# EEZ_PSU_power_board_r5B6b.net
KiCad netlist of a schematic drawn in EAGLE
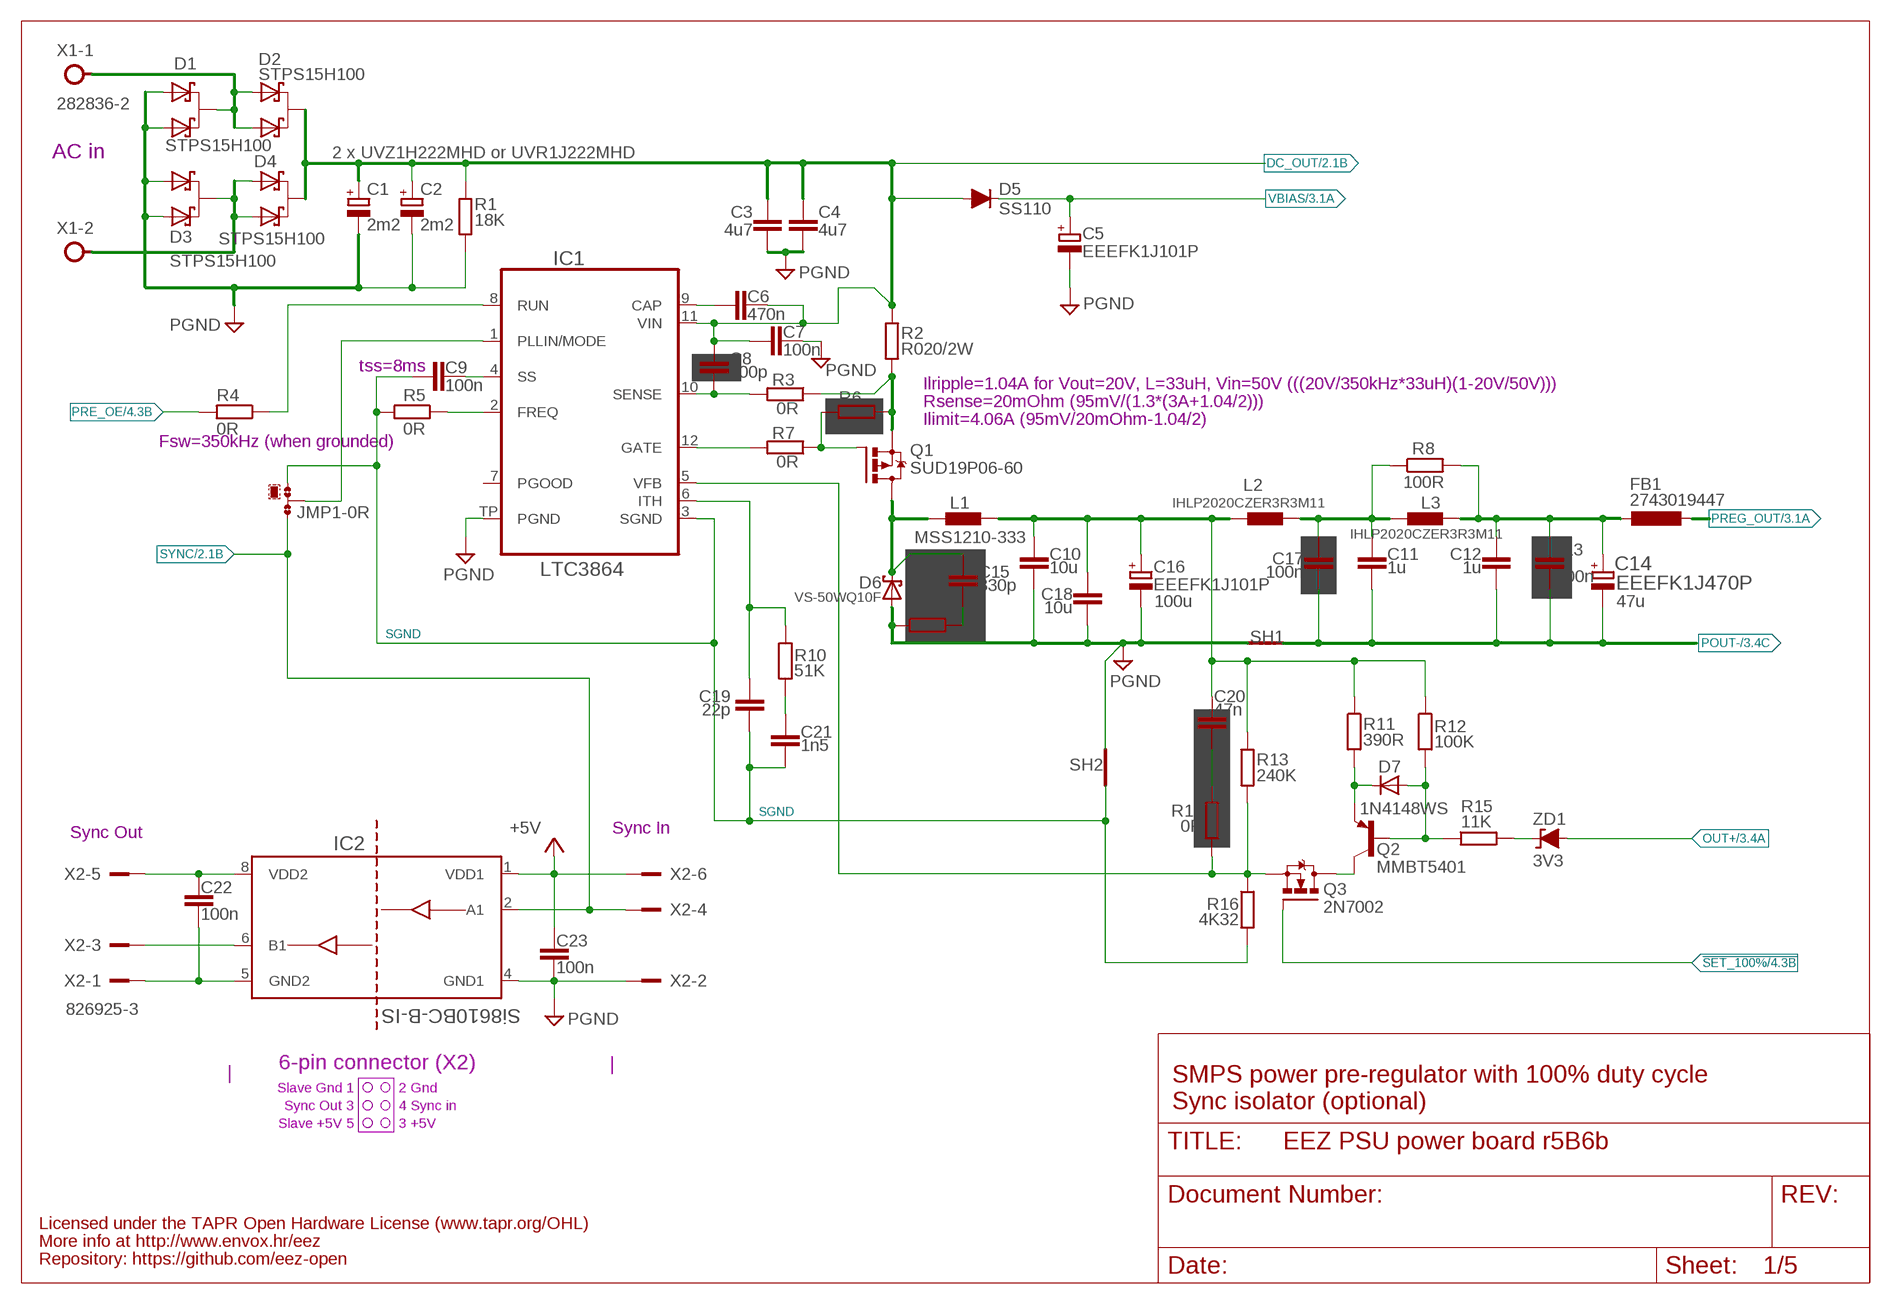
[diagram p0: schematic, sheet 1]
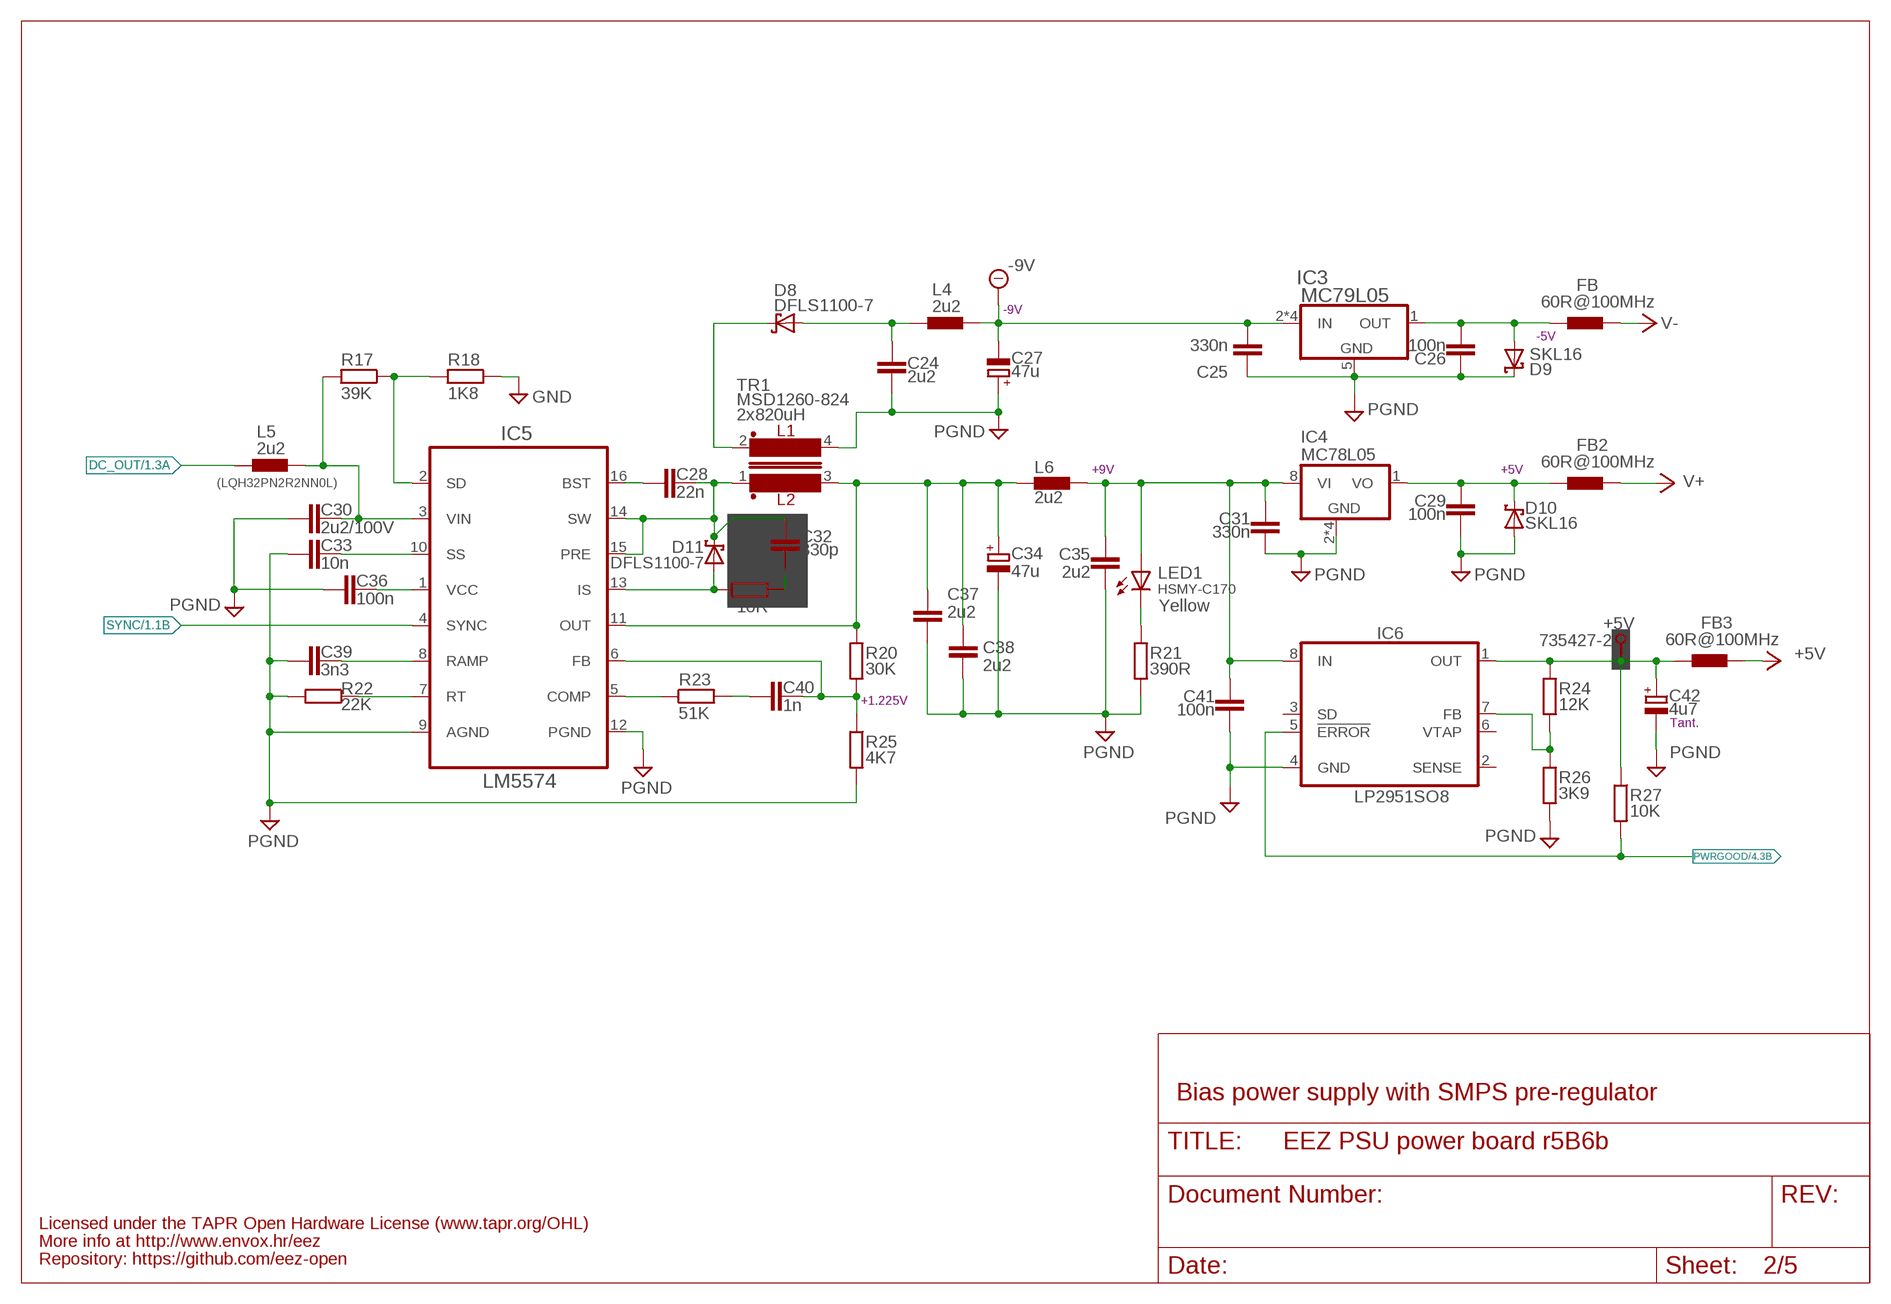
[diagram p1: schematic, sheet 2]
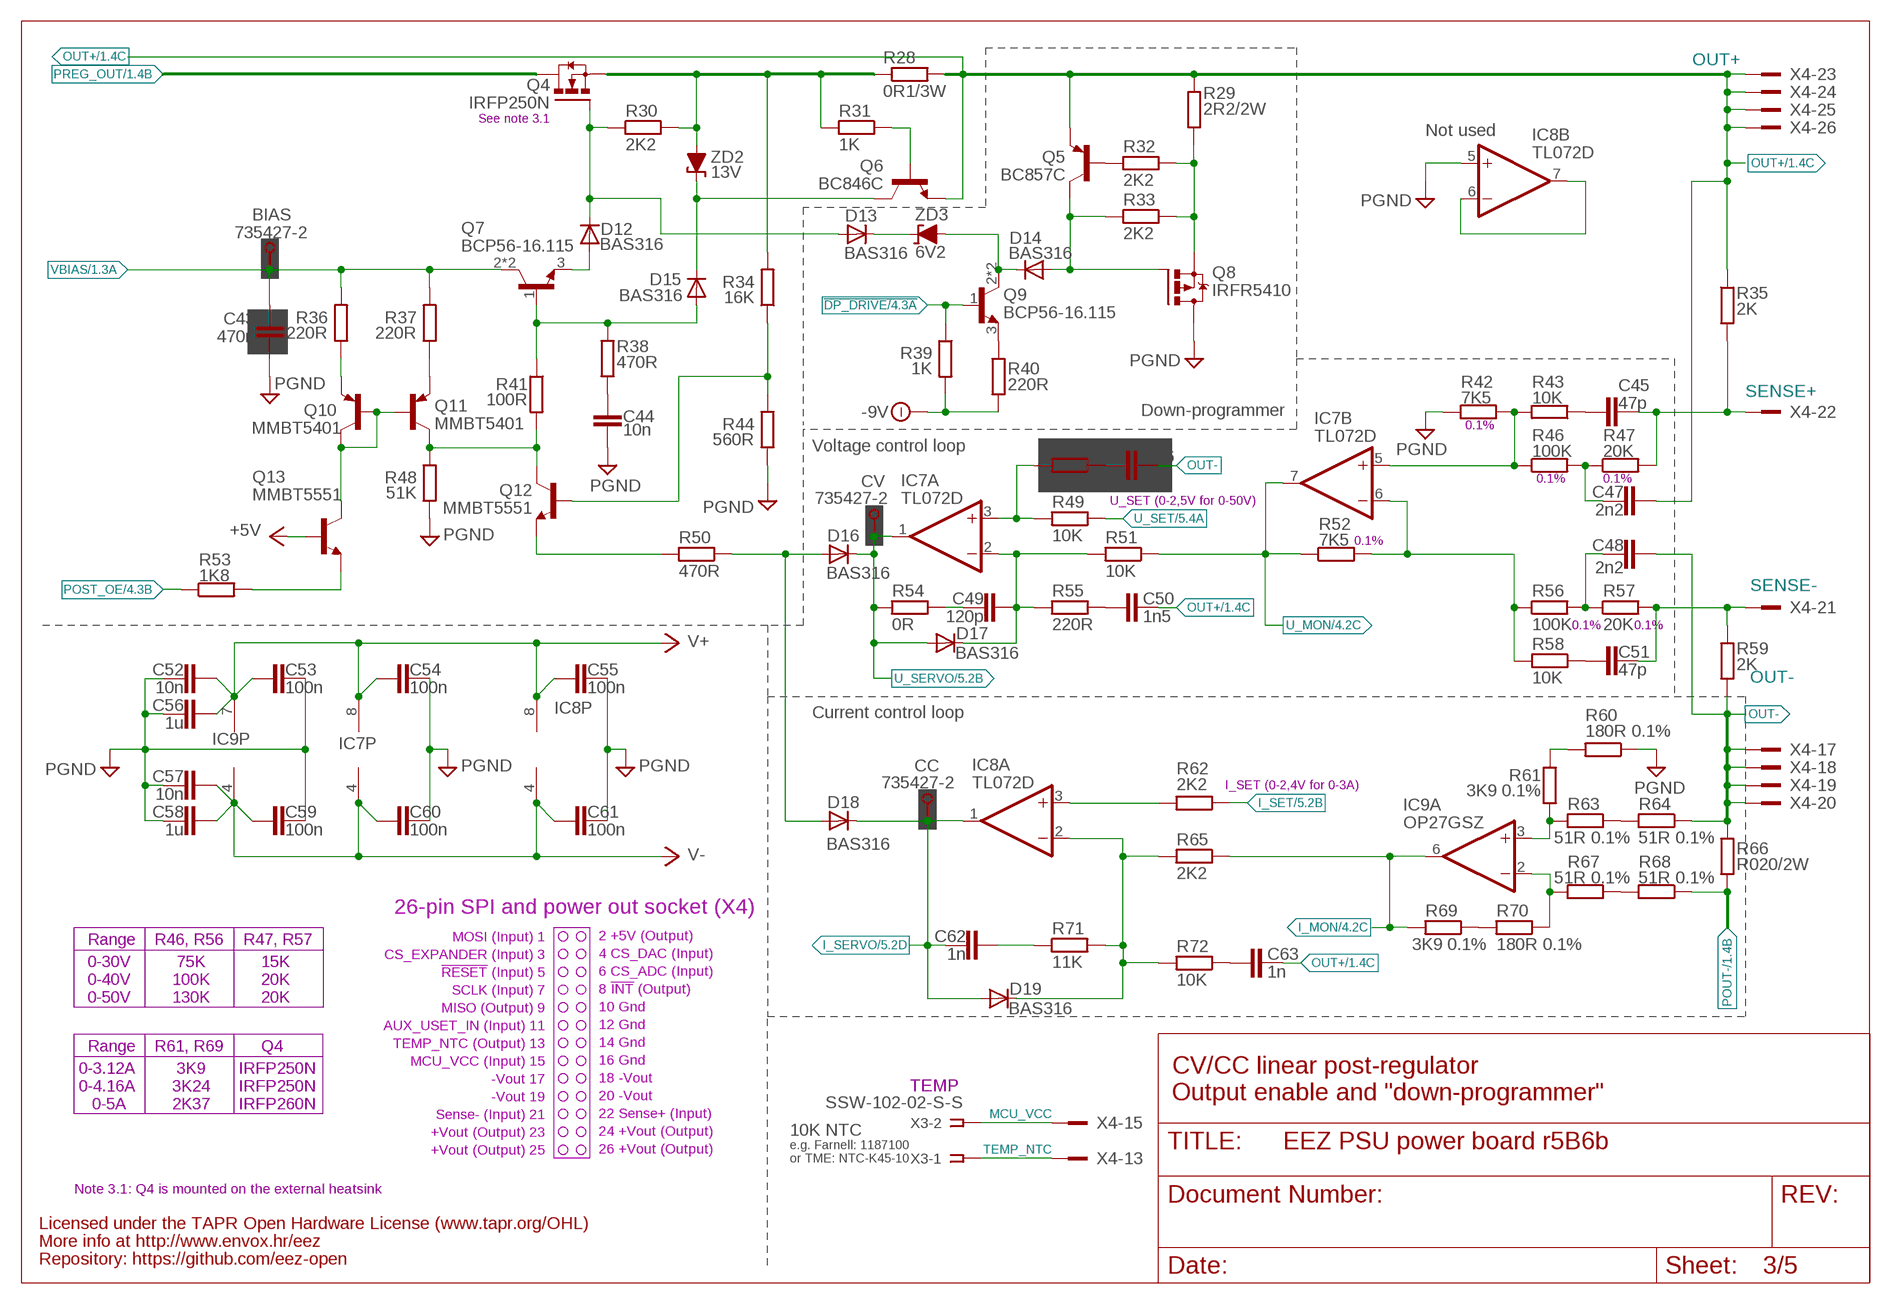
[diagram p2: schematic, sheet 3]
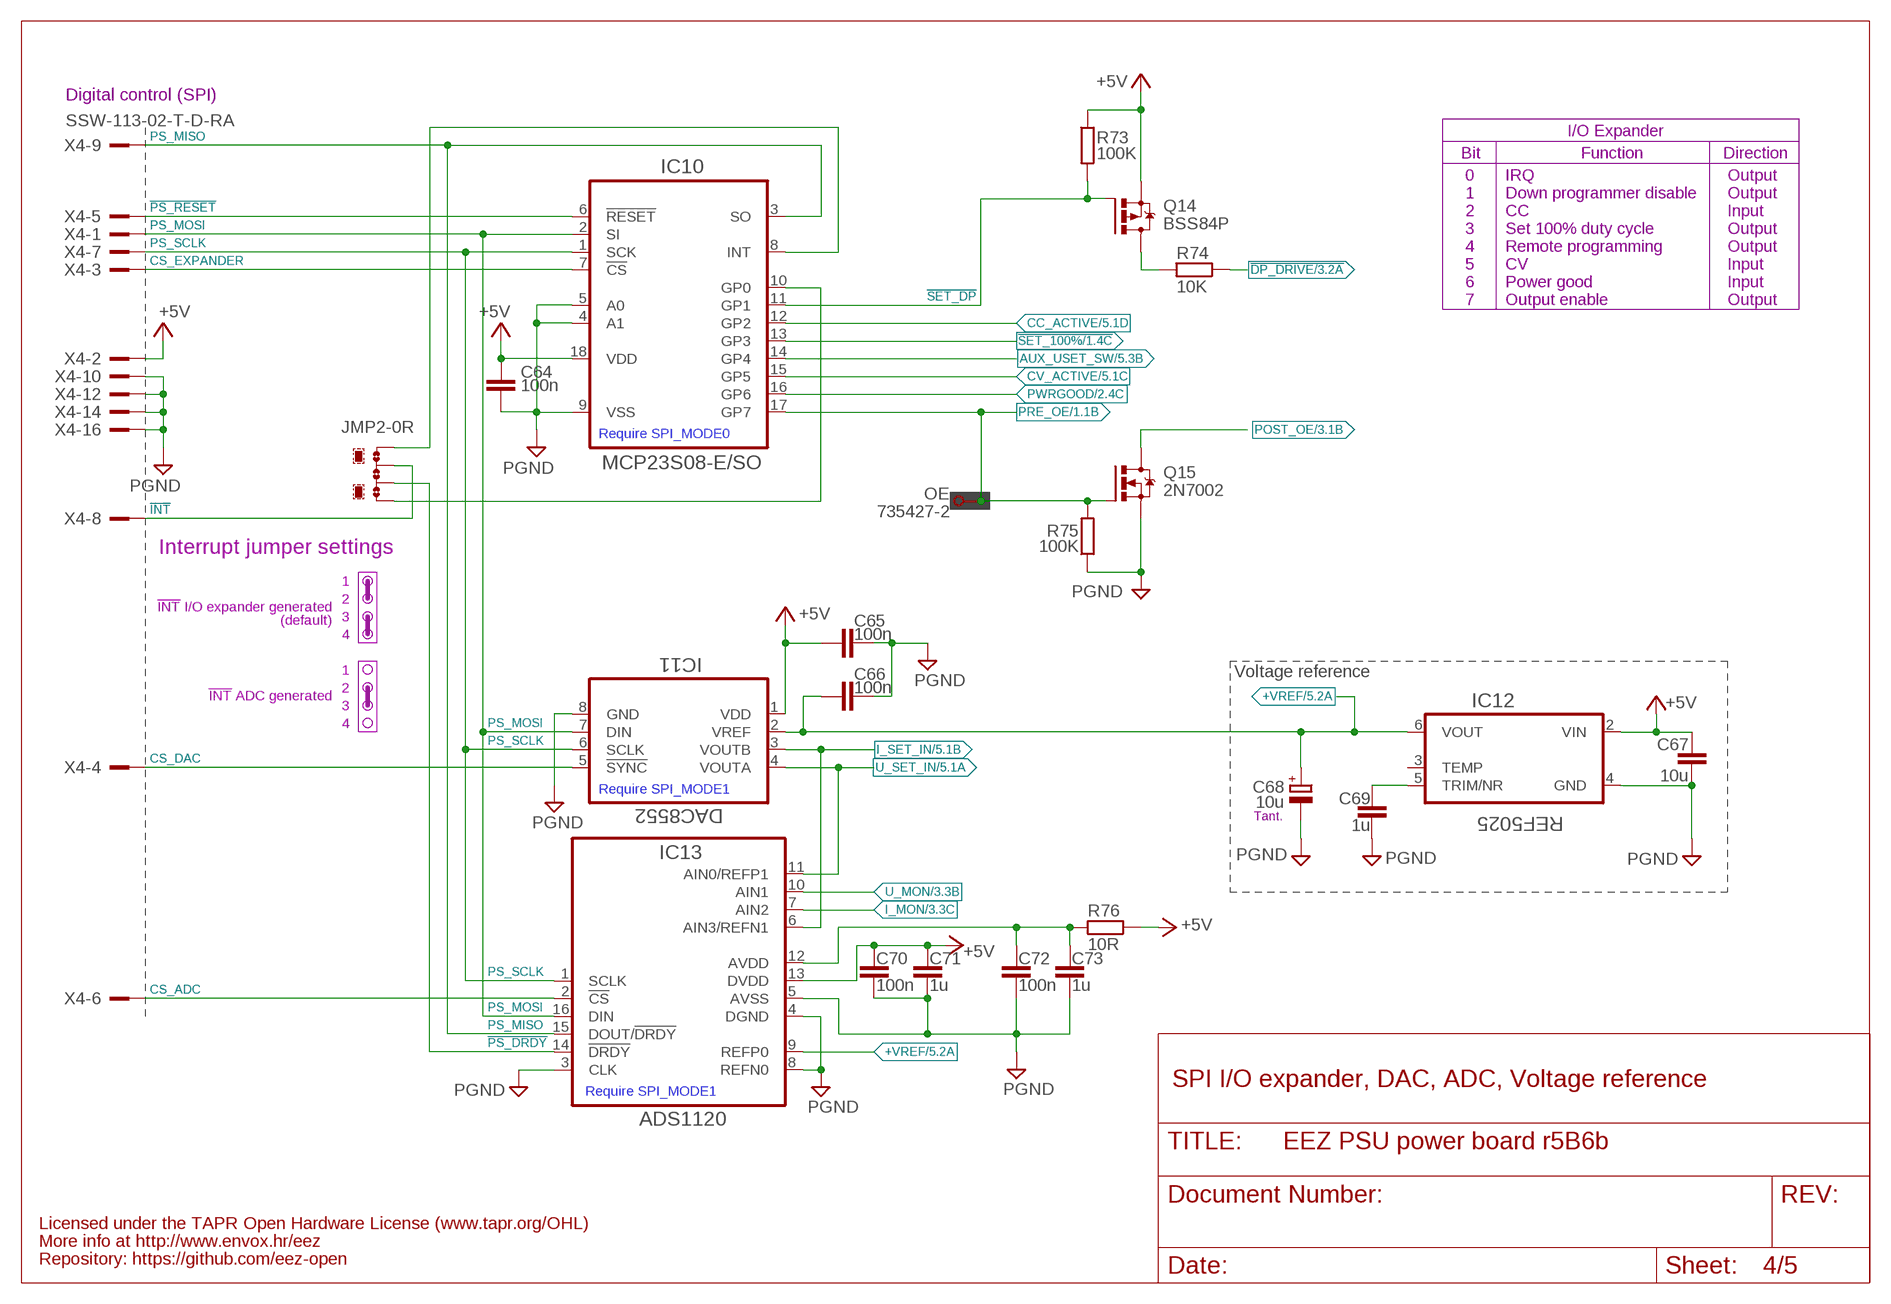
[diagram p3: schematic, sheet 4]
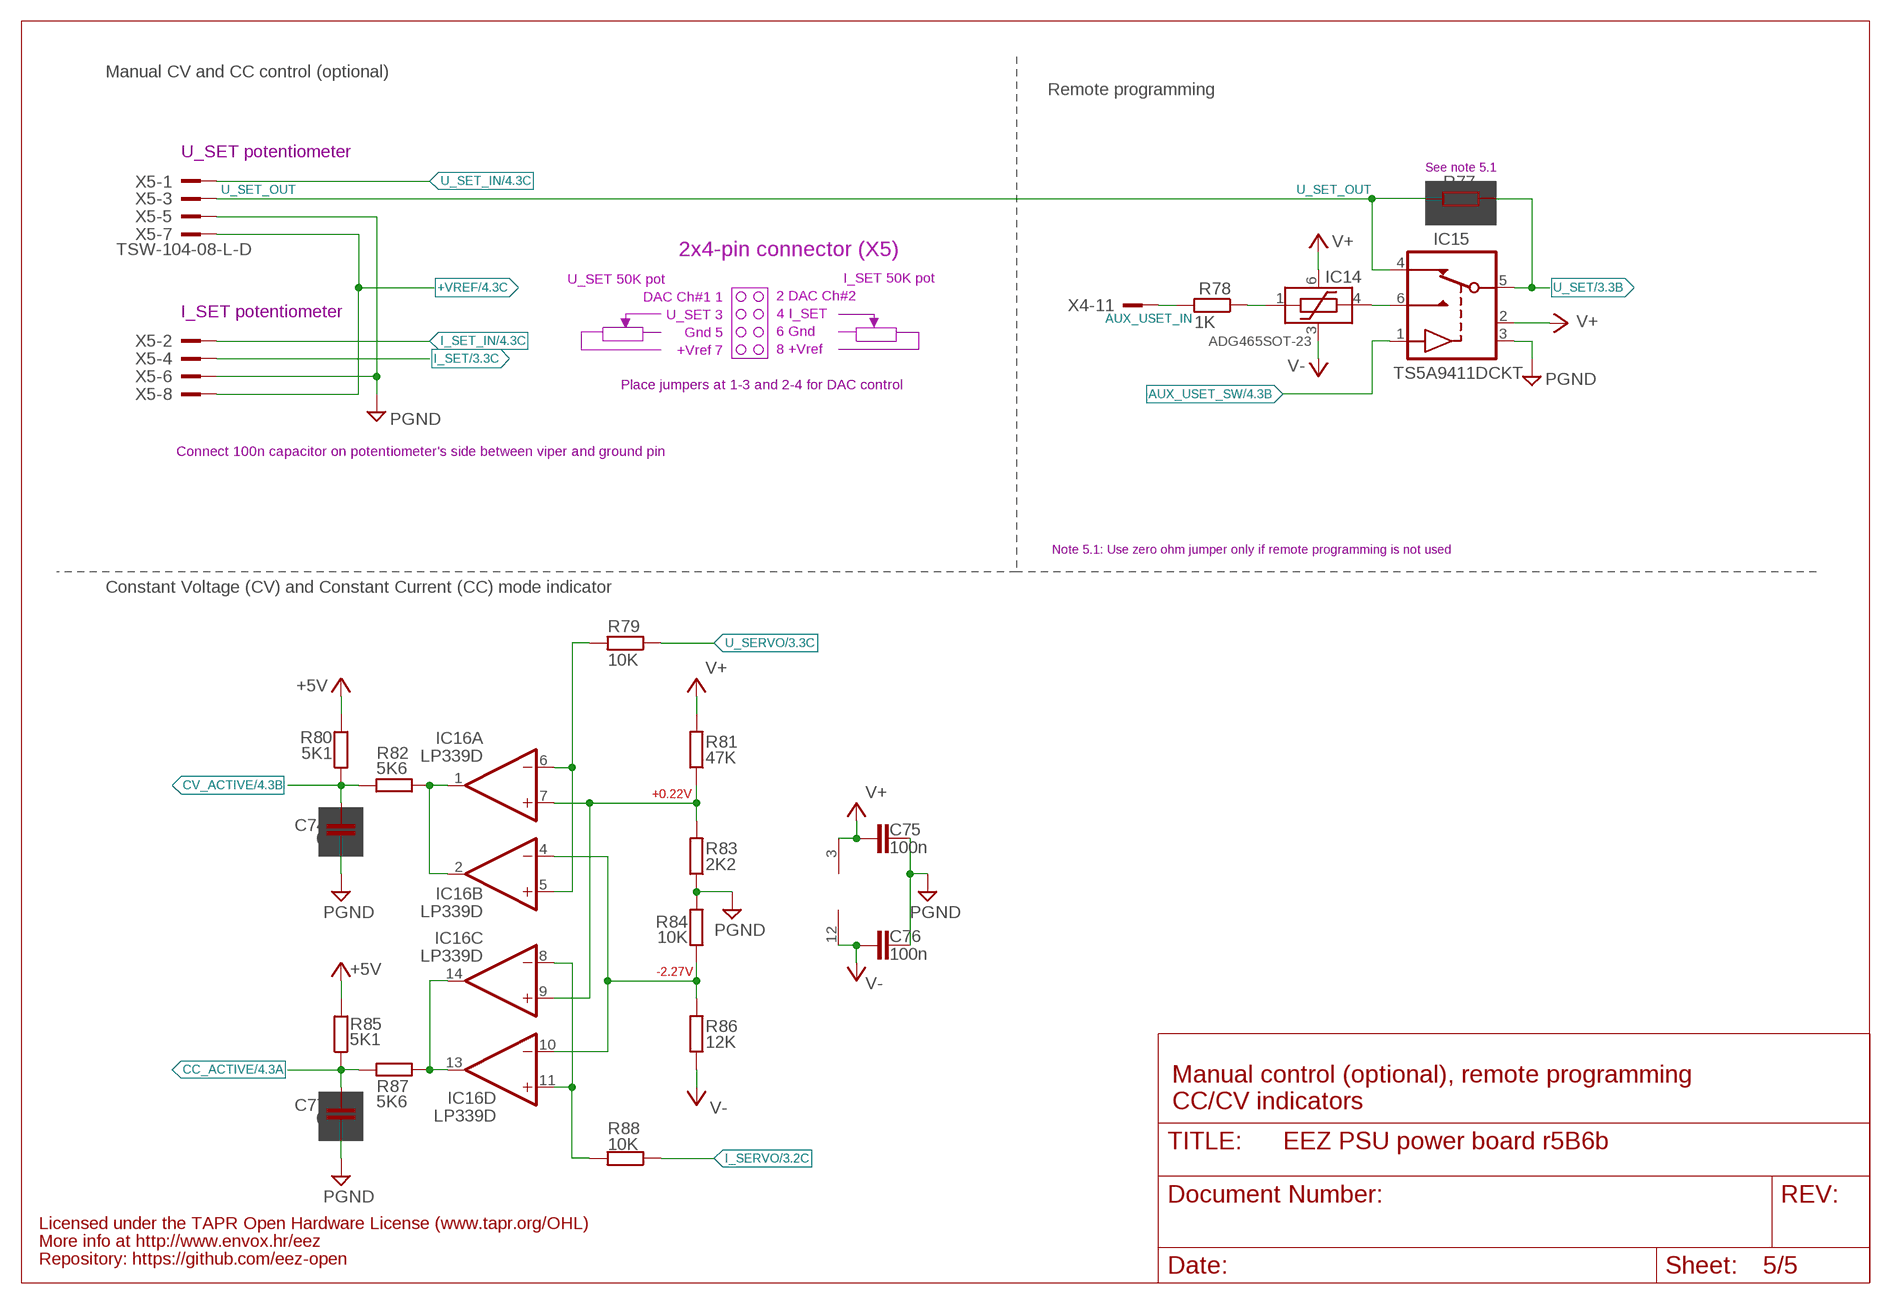
[diagram p4: schematic, sheet 5]

(export (version "E")
  (design (tool "Eeschema 10.0.6"))
  (components
    (comp (ref "C74")
      (value "0")
      (footprint "eagle-import:C0603")
      (libsource (lib "eagle-import") (part "C-EUC0603"))
    )
    (comp (ref "C75")
      (value "100n")
      (footprint "eagle-import:C0603")
      (libsource (lib "eagle-import") (part "C-EUC0603"))
    )
    (comp (ref "C76")
      (value "100n")
      (footprint "eagle-import:C0603")
      (libsource (lib "eagle-import") (part "C-EUC0603"))
    )
    (comp (ref "C77")
      (value "0")
      (footprint "eagle-import:C0603")
      (libsource (lib "eagle-import") (part "C-EUC0603"))
    )
    (comp (ref "IC14")
      (value "ADG465SOT-23")
      (footprint "eagle-import:SOT95P280X145-6N")
      (libsource (lib "eagle-import") (part "ADG465SOT-23"))
    )
    (comp (ref "IC15")
      (value "TS5A9411DCKT")
      (footprint "eagle-import:SOT65P210X110-6N")
      (libsource (lib "eagle-import") (part "TS5A9411DCKT"))
    )
    (comp (ref "IC16")
      (value "LP339D")
      (footprint "eagle-import:SOIC127P600X175-14N")
      (libsource (lib "eagle-import") (part "LM339SO14"))
    )
    (comp (ref "R77")
      (value "0R")
      (footprint "eagle-import:R0805")
      (libsource (lib "eagle-import") (part "R-EU_R0805"))
    )
    (comp (ref "R78")
      (value "1K")
      (footprint "eagle-import:R0805")
      (libsource (lib "eagle-import") (part "R-EU_R0805"))
    )
    (comp (ref "R79")
      (value "10K")
      (footprint "eagle-import:R0805")
      (libsource (lib "eagle-import") (part "R-EU_R0805"))
    )
    (comp (ref "R80")
      (value "5K1")
      (footprint "eagle-import:R0805")
      (libsource (lib "eagle-import") (part "R-EU_R0805"))
    )
    (comp (ref "R81")
      (value "47K")
      (footprint "eagle-import:R0805")
      (libsource (lib "eagle-import") (part "R-EU_R0805"))
    )
    (comp (ref "R82")
      (value "5K6")
      (footprint "eagle-import:R0805")
      (libsource (lib "eagle-import") (part "R-EU_R0805"))
    )
    (comp (ref "R83")
      (value "2K2")
      (footprint "eagle-import:R0805")
      (libsource (lib "eagle-import") (part "R-EU_R0805"))
    )
    (comp (ref "R84")
      (value "10K")
      (footprint "eagle-import:R0805")
      (libsource (lib "eagle-import") (part "R-EU_R0805"))
    )
    (comp (ref "R85")
      (value "5K1")
      (footprint "eagle-import:R0805")
      (libsource (lib "eagle-import") (part "R-EU_R0805"))
    )
    (comp (ref "R86")
      (value "12K")
      (footprint "eagle-import:R0805")
      (libsource (lib "eagle-import") (part "R-EU_R0805"))
    )
    (comp (ref "R87")
      (value "5K6")
      (footprint "eagle-import:R0805")
      (libsource (lib "eagle-import") (part "R-EU_R0805"))
    )
    (comp (ref "R88")
      (value "10K")
      (footprint "eagle-import:R0805")
      (libsource (lib "eagle-import") (part "R-EU_R0805"))
    )
    (comp (ref "X4")
      (value "SSW-113-02-T-D-RA")
      (footprint "eagle-import:SSW-113-02-T-D-RA")
      (fields (field (name "FARNELL") "1805583"))
      (libsource (lib "eagle-import") (part "SSW-113-02-T-D-RA"))
    )
    (comp (ref "X5")
      (value "TSW-104-08-L-D")
      (footprint "eagle-import:TSW-104-02-S-D")
      (libsource (lib "eagle-import") (part "TSW-104-02-S-D"))
    )
    (comp (ref "C1")
      (value "2m2")
      (footprint "eagle-import:ECAP7.5_18")
      (libsource (lib "eagle-import") (part "ECAP7.5G_18MM"))
    )
    (comp (ref "C2")
      (value "2m2")
      (footprint "eagle-import:ECAP7.5_18")
      (libsource (lib "eagle-import") (part "ECAP7.5G_18MM"))
    )
    (comp (ref "C3")
      (value "4u7")
      (footprint "eagle-import:C1210")
      (libsource (lib "eagle-import") (part "C-EUC1210"))
    )
    (comp (ref "C4")
      (value "4u7")
      (footprint "eagle-import:C1210")
      (libsource (lib "eagle-import") (part "C-EUC1210"))
    )
    (comp (ref "C5")
      (value "EEEFK1J101P")
      (footprint "eagle-import:ECAP5_10.5+PANASONIC_F")
      (libsource (lib "eagle-import") (part "ECAP5G_10.5MM_F"))
    )
    (comp (ref "C6")
      (value "470n")
      (footprint "eagle-import:C0805")
      (libsource (lib "eagle-import") (part "C-EUC0805"))
    )
    (comp (ref "C7")
      (value "100n")
      (footprint "eagle-import:C0805")
      (libsource (lib "eagle-import") (part "C-EUC0805"))
    )
    (comp (ref "C8")
      (value "100p")
      (footprint "eagle-import:C0805")
      (libsource (lib "eagle-import") (part "C-EUC0805"))
    )
    (comp (ref "C9")
      (value "100n")
      (footprint "eagle-import:C0805")
      (libsource (lib "eagle-import") (part "C-EUC0805"))
    )
    (comp (ref "C10")
      (value "10u")
      (footprint "eagle-import:C1210")
      (libsource (lib "eagle-import") (part "C-EUC1210"))
    )
    (comp (ref "C11")
      (value "1u")
      (footprint "eagle-import:C1206")
      (libsource (lib "eagle-import") (part "resistor_C-EUC1206"))
    )
    (comp (ref "C12")
      (value "1u")
      (footprint "eagle-import:C1206")
      (libsource (lib "eagle-import") (part "resistor_C-EUC1206"))
    )
    (comp (ref "C13")
      (value "100n")
      (footprint "eagle-import:C0805")
      (libsource (lib "eagle-import") (part "C-EUC0805"))
    )
    (comp (ref "C14")
      (value "EEEFK1J470P")
      (footprint "eagle-import:CAPAE830X1050N")
      (fields (field (name "MPN") "EEE-FK1J470P") (field (name "TOLERANCE") "±20 %"))
      (libsource (lib "eagle-import") (part "EEE--CASE-FFK1J470P"))
    )
    (comp (ref "C15")
      (value "330p")
      (footprint "eagle-import:C0805")
      (libsource (lib "eagle-import") (part "C-EUC0805"))
    )
    (comp (ref "C16")
      (value "EEEFK1J101P")
      (footprint "eagle-import:ECAP5_10.5+PANASONIC_F")
      (libsource (lib "eagle-import") (part "ECAP5G_10.5MM_F"))
    )
    (comp (ref "C17")
      (value "100n")
      (footprint "eagle-import:C0805")
      (libsource (lib "eagle-import") (part "C-EUC0805"))
    )
    (comp (ref "C18")
      (value "10u")
      (footprint "eagle-import:C1210")
      (libsource (lib "eagle-import") (part "C-EUC1210"))
    )
    (comp (ref "C19")
      (value "22p")
      (footprint "eagle-import:C0805")
      (libsource (lib "eagle-import") (part "C-EUC0805"))
    )
    (comp (ref "C20")
      (value "47n")
      (footprint "eagle-import:C0805")
      (libsource (lib "eagle-import") (part "C-EUC0805"))
    )
    (comp (ref "C21")
      (value "1n5")
      (footprint "eagle-import:C0805")
      (libsource (lib "eagle-import") (part "C-EUC0805"))
    )
    (comp (ref "C22")
      (value "100n")
      (footprint "eagle-import:C0603")
      (libsource (lib "eagle-import") (part "C-EUC0603"))
    )
    (comp (ref "C23")
      (value "100n")
      (footprint "eagle-import:C0603")
      (libsource (lib "eagle-import") (part "C-EUC0603"))
    )
    (comp (ref "D1")
      (value "STPS15H100")
      (footprint "eagle-import:TO252@1")
      (libsource (lib "eagle-import") (part "VS-6CWQ06FNPBF"))
    )
    (comp (ref "D2")
      (value "STPS15H100")
      (footprint "eagle-import:TO252@1")
      (libsource (lib "eagle-import") (part "VS-6CWQ06FNPBF"))
    )
    (comp (ref "D3")
      (value "STPS15H100")
      (footprint "eagle-import:TO252@1")
      (libsource (lib "eagle-import") (part "VS-6CWQ06FNPBF"))
    )
    (comp (ref "D4")
      (value "STPS15H100")
      (footprint "eagle-import:TO252@1")
      (libsource (lib "eagle-import") (part "VS-6CWQ06FNPBF"))
    )
    (comp (ref "D5")
      (value "SS110")
      (footprint "eagle-import:DO214AA")
      (libsource (lib "eagle-import") (part "DIODEDO214AA"))
    )
    (comp (ref "D6")
      (value "VS-50WQ10F")
      (footprint "eagle-import:TO252@1")
      (libsource (lib "eagle-import") (part "SCHOTTKYTO252"))
    )
    (comp (ref "D7")
      (value "1N4148WS")
      (footprint "eagle-import:SOD323-W")
      (libsource (lib "eagle-import") (part "DIODE-SOD323-W"))
    )
    (comp (ref "FB1")
      (value "2743019447")
      (footprint "eagle-import:L1812")
      (libsource (lib "eagle-import") (part "L-EUL1812"))
    )
    (comp (ref "IC1")
      (value "LTC3864")
      (footprint "eagle-import:LTC_05-08-1666")
      (libsource (lib "eagle-import") (part "LTC3864"))
    )
    (comp (ref "IC2")
      (value "Si8610BC-B-IS")
      (footprint "eagle-import:SOIC127P600X173-8N")
      (libsource (lib "eagle-import") (part "SI8610"))
    )
    (comp (ref "JMP1")
      (value "0R-JUMPA")
      (footprint "eagle-import:A0R-JMP")
      (libsource (lib "eagle-import") (part "0R-JUMPA"))
    )
    (comp (ref "L1")
      (value "MSS1210-333")
      (footprint "eagle-import:MSS1210")
      (libsource (lib "eagle-import") (part "COILCRAFT_MSS1210"))
    )
    (comp (ref "L2")
      (value "IHLP2020CZER3R3M11")
      (footprint "eagle-import:IHLP-2020BZ-11")
      (libsource (lib "eagle-import") (part "IHLP-2020BZ-11"))
    )
    (comp (ref "L3")
      (value "IHLP2020CZER3R3M11")
      (footprint "eagle-import:IHLP-2020BZ-11")
      (libsource (lib "eagle-import") (part "IHLP-2020BZ-11"))
    )
    (comp (ref "Q1")
      (value "SUD19P06-60")
      (footprint "eagle-import:TO229P990X239-3N")
      (libsource (lib "eagle-import") (part "P-MOSFETDPAK"))
    )
    (comp (ref "Q2")
      (value "MMBT5401")
      (footprint "eagle-import:SOT23-BEC")
      (libsource (lib "eagle-import") (part "-PNP-SOT23-BECBC857B"))
    )
    (comp (ref "Q3")
      (value "2N7002")
      (footprint "eagle-import:SOT103P240X110-3N")
      (fields (field (name "MPN") "2N7002-7-F"))
      (libsource (lib "eagle-import") (part "2N7002"))
    )
    (comp (ref "R1")
      (value "18K")
      (footprint "eagle-import:R1206")
      (libsource (lib "eagle-import") (part "R-EU_R1206"))
    )
    (comp (ref "R2")
      (value "R020/2W")
      (footprint "eagle-import:R2512")
      (libsource (lib "eagle-import") (part "R-EU_R2512"))
    )
    (comp (ref "R3")
      (value "0R")
      (footprint "eagle-import:R0805")
      (libsource (lib "eagle-import") (part "R-EU_R0805"))
    )
    (comp (ref "R4")
      (value "0R")
      (footprint "eagle-import:R0805")
      (libsource (lib "eagle-import") (part "R-EU_R0805"))
    )
    (comp (ref "R5")
      (value "0R")
      (footprint "eagle-import:R0805")
      (libsource (lib "eagle-import") (part "R-EU_R0805"))
    )
    (comp (ref "R6")
      (value "100K")
      (footprint "eagle-import:R0805")
      (libsource (lib "eagle-import") (part "R-EU_R0805"))
    )
    (comp (ref "R7")
      (value "0R")
      (footprint "eagle-import:R0805")
      (libsource (lib "eagle-import") (part "R-EU_R0805"))
    )
    (comp (ref "R8")
      (value "100R")
      (footprint "eagle-import:R0805")
      (libsource (lib "eagle-import") (part "R-EU_R0805"))
    )
    (comp (ref "R9")
      (value "10R")
      (footprint "eagle-import:R1206")
      (libsource (lib "eagle-import") (part "R-EU_R1206"))
    )
    (comp (ref "R10")
      (value "51K")
      (footprint "eagle-import:R0805")
      (libsource (lib "eagle-import") (part "R-EU_R0805"))
    )
    (comp (ref "R11")
      (value "390R")
      (footprint "eagle-import:R0805")
      (libsource (lib "eagle-import") (part "R-EU_R0805"))
    )
    (comp (ref "R12")
      (value "100K")
      (footprint "eagle-import:R0805")
      (libsource (lib "eagle-import") (part "R-EU_R0805"))
    )
    (comp (ref "R13")
      (value "240K")
      (footprint "eagle-import:R0805")
      (libsource (lib "eagle-import") (part "R-EU_R0805"))
    )
    (comp (ref "R14")
      (value "0R")
      (footprint "eagle-import:R0805")
      (libsource (lib "eagle-import") (part "R-EU_R0805"))
    )
    (comp (ref "R15")
      (value "11K")
      (footprint "eagle-import:R0805")
      (libsource (lib "eagle-import") (part "R-EU_R0805"))
    )
    (comp (ref "R16")
      (value "4K32")
      (footprint "eagle-import:R0805")
      (libsource (lib "eagle-import") (part "R-EU_R0805"))
    )
    (comp (ref "SH1")
      (value "Pgnd to Pout- short")
      (footprint "eagle-import:SHORT")
      (libsource (lib "eagle-import") (part "SHORT"))
    )
    (comp (ref "SH2")
      (value "Sgnd to Pgnd short")
      (footprint "eagle-import:SHORT")
      (libsource (lib "eagle-import") (part "SHORT"))
    )
    (comp (ref "X1")
      (value "282836-2")
      (footprint "eagle-import:TBLOCK5.0_2")
      (libsource (lib "eagle-import") (part "TBLOCK5.0_2A"))
    )
    (comp (ref "X2")
      (value "826925-3")
      (footprint "eagle-import:TSW-103-07-F-D")
      (libsource (lib "eagle-import") (part "TSW-103-07-F-D"))
    )
    (comp (ref "ZD1")
      (value "3V3")
      (footprint "eagle-import:MINIMELF")
      (libsource (lib "eagle-import") (part "ZENER-DIODEMINIMELF"))
    )
    (comp (ref "BIAS")
      (value "735427-2")
      (footprint "eagle-import:PCB_SHIELD_TAB")
      (libsource (lib "eagle-import") (part "PCB_TEST_TABSHIELD"))
    )
    (comp (ref "C43")
      (value "470n")
      (footprint "eagle-import:C1812")
      (libsource (lib "eagle-import") (part "C-EUC1812"))
    )
    (comp (ref "C44")
      (value "10n")
      (footprint "eagle-import:C0805")
      (libsource (lib "eagle-import") (part "C-EUC0805"))
    )
    (comp (ref "C45")
      (value "47p")
      (footprint "eagle-import:C0805")
      (libsource (lib "eagle-import") (part "C-EUC0805"))
    )
    (comp (ref "C46")
      (value "1n5")
      (footprint "eagle-import:C0805")
      (libsource (lib "eagle-import") (part "C-EUC0805"))
    )
    (comp (ref "C47")
      (value "2n2")
      (footprint "eagle-import:C0805")
      (libsource (lib "eagle-import") (part "C-EUC0805"))
    )
    (comp (ref "C48")
      (value "2n2")
      (footprint "eagle-import:C0805")
      (libsource (lib "eagle-import") (part "C-EUC0805"))
    )
    (comp (ref "C49")
      (value "120p")
      (footprint "eagle-import:C0805")
      (libsource (lib "eagle-import") (part "C-EUC0805"))
    )
    (comp (ref "C50")
      (value "1n5")
      (footprint "eagle-import:C0805")
      (libsource (lib "eagle-import") (part "C-EUC0805"))
    )
    (comp (ref "C51")
      (value "47p")
      (footprint "eagle-import:C0805")
      (libsource (lib "eagle-import") (part "C-EUC0805"))
    )
    (comp (ref "C52")
      (value "10n")
      (footprint "eagle-import:C0805")
      (libsource (lib "eagle-import") (part "C-EUC0805"))
    )
    (comp (ref "C53")
      (value "100n")
      (footprint "eagle-import:C0603")
      (libsource (lib "eagle-import") (part "C-EUC0603"))
    )
    (comp (ref "C54")
      (value "100n")
      (footprint "eagle-import:C0603")
      (libsource (lib "eagle-import") (part "C-EUC0603"))
    )
    (comp (ref "C55")
      (value "100n")
      (footprint "eagle-import:C0603")
      (libsource (lib "eagle-import") (part "C-EUC0603"))
    )
    (comp (ref "C56")
      (value "1u")
      (footprint "eagle-import:C0805")
      (libsource (lib "eagle-import") (part "C-EUC0805"))
    )
    (comp (ref "C57")
      (value "10n")
      (footprint "eagle-import:C0805")
      (libsource (lib "eagle-import") (part "C-EUC0805"))
    )
    (comp (ref "C58")
      (value "1u")
      (footprint "eagle-import:C0805")
      (libsource (lib "eagle-import") (part "C-EUC0805"))
    )
    (comp (ref "C59")
      (value "100n")
      (footprint "eagle-import:C0603")
      (libsource (lib "eagle-import") (part "C-EUC0603"))
    )
    (comp (ref "C60")
      (value "100n")
      (footprint "eagle-import:C0603")
      (libsource (lib "eagle-import") (part "C-EUC0603"))
    )
    (comp (ref "C61")
      (value "100n")
      (footprint "eagle-import:C0603")
      (libsource (lib "eagle-import") (part "C-EUC0603"))
    )
    (comp (ref "C62")
      (value "1n")
      (footprint "eagle-import:C0805")
      (libsource (lib "eagle-import") (part "C-EUC0805"))
    )
    (comp (ref "C63")
      (value "1n")
      (footprint "eagle-import:C0805")
      (libsource (lib "eagle-import") (part "C-EUC0805"))
    )
    (comp (ref "CC")
      (value "735427-2")
      (footprint "eagle-import:PCB_SHIELD_TAB")
      (libsource (lib "eagle-import") (part "PCB_TEST_TABSHIELD"))
    )
    (comp (ref "CV")
      (value "735427-2")
      (footprint "eagle-import:PCB_SHIELD_TAB")
      (libsource (lib "eagle-import") (part "PCB_TEST_TABSHIELD"))
    )
    (comp (ref "D12")
      (value "BAS316")
      (footprint "eagle-import:SOD323-W")
      (libsource (lib "eagle-import") (part "DIODE-SOD323-W"))
    )
    (comp (ref "D13")
      (value "BAS316")
      (footprint "eagle-import:SOD323-W")
      (libsource (lib "eagle-import") (part "DIODE-SOD323-W"))
    )
    (comp (ref "D14")
      (value "BAS316")
      (footprint "eagle-import:SOD323-W")
      (libsource (lib "eagle-import") (part "DIODE-SOD323-W"))
    )
    (comp (ref "D15")
      (value "BAS316")
      (footprint "eagle-import:SOD323-W")
      (libsource (lib "eagle-import") (part "DIODE-SOD323-W"))
    )
    (comp (ref "D16")
      (value "BAS316")
      (footprint "eagle-import:SOD323-W")
      (libsource (lib "eagle-import") (part "DIODE-SOD323-W"))
    )
    (comp (ref "D17")
      (value "BAS316")
      (footprint "eagle-import:SOD323-W")
      (libsource (lib "eagle-import") (part "DIODE-SOD323-W"))
    )
    (comp (ref "D18")
      (value "BAS316")
      (footprint "eagle-import:SOD323-W")
      (libsource (lib "eagle-import") (part "DIODE-SOD323-W"))
    )
    (comp (ref "D19")
      (value "BAS316")
      (footprint "eagle-import:SOD323-W")
      (libsource (lib "eagle-import") (part "DIODE-SOD323-W"))
    )
    (comp (ref "IC7")
      (value "TL072D")
      (footprint "eagle-import:SOIC127P600X173-8N")
      (libsource (lib "eagle-import") (part "TL072SOIC8"))
    )
    (comp (ref "IC8")
      (value "TL072D")
      (footprint "eagle-import:SOIC127P600X173-8N")
      (libsource (lib "eagle-import") (part "TL072SOIC8"))
    )
    (comp (ref "IC9")
      (value "OP27GSZ")
      (footprint "eagle-import:SOIC127P600X173-8N")
      (libsource (lib "eagle-import") (part "OP27GSZSO8"))
    )
    (comp (ref "Q4")
      (value "IRFP250N")
      (footprint "eagle-import:TO247BH-CLR")
      (libsource (lib "eagle-import") (part "IRFP240BOTTOM"))
    )
    (comp (ref "Q5")
      (value "BC857C")
      (footprint "eagle-import:SOT23-BEC")
      (libsource (lib "eagle-import") (part "-PNP-SOT23-BECBC857C"))
    )
    (comp (ref "Q6")
      (value "BC846C")
      (footprint "eagle-import:SOT23-BEC")
      (libsource (lib "eagle-import") (part "-NPN-SOT23-BECBC846B"))
    )
    (comp (ref "Q7")
      (value "BCP56-16.115")
      (footprint "eagle-import:SOT230P700X180-4N")
      (libsource (lib "eagle-import") (part "BCP56"))
    )
    (comp (ref "Q8")
      (value "IRFR5410")
      (footprint "eagle-import:TO229P990X239-3N")
      (libsource (lib "eagle-import") (part "P-MOSFETDPAK"))
    )
    (comp (ref "Q9")
      (value "BCP56-16.115")
      (footprint "eagle-import:SOT230P700X180-4N")
      (libsource (lib "eagle-import") (part "BCP56"))
    )
    (comp (ref "Q10")
      (value "MMBT5401")
      (footprint "eagle-import:SOT23-BEC")
      (libsource (lib "eagle-import") (part "-PNP-SOT23-BECBC857B"))
    )
    (comp (ref "Q11")
      (value "MMBT5401")
      (footprint "eagle-import:SOT23-BEC")
      (libsource (lib "eagle-import") (part "-PNP-SOT23-BECBC857B"))
    )
    (comp (ref "Q12")
      (value "MMBT5551")
      (footprint "eagle-import:SOT23-BEC")
      (libsource (lib "eagle-import") (part "-NPN-SOT23-BECMMBT5551LT1"))
    )
    (comp (ref "Q13")
      (value "MMBT5551")
      (footprint "eagle-import:SOT23-BEC")
      (libsource (lib "eagle-import") (part "-NPN-SOT23-BECMMBT5551LT1"))
    )
    (comp (ref "R28")
      (value "0R1/3W")
      (footprint "eagle-import:R_2512+0411_15")
      (libsource (lib "eagle-import") (part "R_EUCOMBO"))
    )
    (comp (ref "R29")
      (value "2R2/2W")
      (footprint "eagle-import:R_2512+0411_15")
      (libsource (lib "eagle-import") (part "R_EUCOMBO"))
    )
    (comp (ref "R30")
      (value "2K2")
      (footprint "eagle-import:R0805")
      (libsource (lib "eagle-import") (part "R-EU_R0805"))
    )
    (comp (ref "R31")
      (value "1K")
      (footprint "eagle-import:R0805")
      (libsource (lib "eagle-import") (part "R-EU_R0805"))
    )
    (comp (ref "R32")
      (value "2K2")
      (footprint "eagle-import:R0805")
      (libsource (lib "eagle-import") (part "R-EU_R0805"))
    )
    (comp (ref "R33")
      (value "2K2")
      (footprint "eagle-import:R0805")
      (libsource (lib "eagle-import") (part "R-EU_R0805"))
    )
    (comp (ref "R34")
      (value "16K")
      (footprint "eagle-import:R0805")
      (libsource (lib "eagle-import") (part "R-EU_R0805"))
    )
    (comp (ref "R35")
      (value "2K")
      (footprint "eagle-import:R0805")
      (libsource (lib "eagle-import") (part "R-EU_R0805"))
    )
    (comp (ref "R36")
      (value "220R")
      (footprint "eagle-import:R0805")
      (libsource (lib "eagle-import") (part "R-EU_R0805"))
    )
    (comp (ref "R37")
      (value "220R")
      (footprint "eagle-import:R0805")
      (libsource (lib "eagle-import") (part "R-EU_R0805"))
    )
    (comp (ref "R38")
      (value "470R")
      (footprint "eagle-import:R0805")
      (libsource (lib "eagle-import") (part "R-EU_R0805"))
    )
    (comp (ref "R39")
      (value "1K")
      (footprint "eagle-import:R0805")
      (libsource (lib "eagle-import") (part "R-EU_R0805"))
    )
    (comp (ref "R40")
      (value "220R")
      (footprint "eagle-import:R0805")
      (libsource (lib "eagle-import") (part "R-EU_R0805"))
    )
    (comp (ref "R41")
      (value "100R")
      (footprint "eagle-import:R0805")
      (libsource (lib "eagle-import") (part "R-EU_R0805"))
    )
    (comp (ref "R42")
      (value "7K5")
      (footprint "eagle-import:R0805")
      (libsource (lib "eagle-import") (part "R-EU_R0805"))
    )
    (comp (ref "R43")
      (value "10K")
      (footprint "eagle-import:R0805")
      (libsource (lib "eagle-import") (part "R-EU_R0805"))
    )
    (comp (ref "R44")
      (value "560R")
      (footprint "eagle-import:R0805")
      (libsource (lib "eagle-import") (part "R-EU_R0805"))
    )
    (comp (ref "R45")
      (value "220R")
      (footprint "eagle-import:R0805")
      (libsource (lib "eagle-import") (part "R-EU_R0805"))
    )
    (comp (ref "R46")
      (value "100K")
      (footprint "eagle-import:R0805")
      (libsource (lib "eagle-import") (part "R-EU_R0805"))
    )
    (comp (ref "R47")
      (value "20K")
      (footprint "eagle-import:R0805")
      (libsource (lib "eagle-import") (part "R-EU_R0805"))
    )
    (comp (ref "R48")
      (value "51K")
      (footprint "eagle-import:R0805")
      (libsource (lib "eagle-import") (part "R-EU_R0805"))
    )
    (comp (ref "R49")
      (value "10K")
      (footprint "eagle-import:R0805")
      (libsource (lib "eagle-import") (part "R-EU_R0805"))
    )
    (comp (ref "R50")
      (value "470R")
      (footprint "eagle-import:R0805")
      (libsource (lib "eagle-import") (part "R-EU_R0805"))
    )
    (comp (ref "R51")
      (value "10K")
      (footprint "eagle-import:R0805")
      (libsource (lib "eagle-import") (part "R-EU_R0805"))
    )
    (comp (ref "R52")
      (value "7K5")
      (footprint "eagle-import:R0805")
      (libsource (lib "eagle-import") (part "R-EU_R0805"))
    )
    (comp (ref "R53")
      (value "1K8")
      (footprint "eagle-import:R0805")
      (libsource (lib "eagle-import") (part "R-EU_R0805"))
    )
    (comp (ref "R54")
      (value "0R")
      (footprint "eagle-import:R0805")
      (libsource (lib "eagle-import") (part "R-EU_R0805"))
    )
    (comp (ref "R55")
      (value "220R")
      (footprint "eagle-import:R0805")
      (libsource (lib "eagle-import") (part "R-EU_R0805"))
    )
    (comp (ref "R56")
      (value "100K")
      (footprint "eagle-import:R0805")
      (libsource (lib "eagle-import") (part "R-EU_R0805"))
    )
    (comp (ref "R57")
      (value "20K")
      (footprint "eagle-import:R0805")
      (libsource (lib "eagle-import") (part "R-EU_R0805"))
    )
    (comp (ref "R58")
      (value "10K")
      (footprint "eagle-import:R0805")
      (libsource (lib "eagle-import") (part "R-EU_R0805"))
    )
    (comp (ref "R59")
      (value "2K")
      (footprint "eagle-import:R0805")
      (libsource (lib "eagle-import") (part "R-EU_R0805"))
    )
    (comp (ref "R60")
      (value "180R 0.1%")
      (footprint "eagle-import:R0805")
      (libsource (lib "eagle-import") (part "R-EU_R0805"))
    )
    (comp (ref "R61")
      (value "3K9 0.1%")
      (footprint "eagle-import:R0805")
      (libsource (lib "eagle-import") (part "R-EU_R0805"))
    )
    (comp (ref "R62")
      (value "2K2")
      (footprint "eagle-import:R0805")
      (libsource (lib "eagle-import") (part "R-EU_R0805"))
    )
    (comp (ref "R63")
      (value "51R 0.1%")
      (footprint "eagle-import:R0805")
      (libsource (lib "eagle-import") (part "R-EU_R0805"))
    )
    (comp (ref "R64")
      (value "51R 0.1%")
      (footprint "eagle-import:R0805")
      (libsource (lib "eagle-import") (part "R-EU_R0805"))
    )
    (comp (ref "R65")
      (value "2K2")
      (footprint "eagle-import:R0805")
      (libsource (lib "eagle-import") (part "R-EU_R0805"))
    )
    (comp (ref "R66")
      (value "R020/2W")
      (footprint "eagle-import:R2512")
      (libsource (lib "eagle-import") (part "R-EU_R2512"))
    )
    (comp (ref "R67")
      (value "51R 0.1%")
      (footprint "eagle-import:R0805")
      (libsource (lib "eagle-import") (part "R-EU_R0805"))
    )
    (comp (ref "R68")
      (value "51R 0.1%")
      (footprint "eagle-import:R0805")
      (libsource (lib "eagle-import") (part "R-EU_R0805"))
    )
    (comp (ref "R69")
      (value "3K9 0.1%")
      (footprint "eagle-import:R0805")
      (libsource (lib "eagle-import") (part "R-EU_R0805"))
    )
    (comp (ref "R70")
      (value "180R 0.1%")
      (footprint "eagle-import:R0805")
      (libsource (lib "eagle-import") (part "R-EU_R0805"))
    )
    (comp (ref "R71")
      (value "11K")
      (footprint "eagle-import:R0805")
      (libsource (lib "eagle-import") (part "R-EU_R0805"))
    )
    (comp (ref "R72")
      (value "10K")
      (footprint "eagle-import:R0805")
      (libsource (lib "eagle-import") (part "R-EU_R0805"))
    )
    (comp (ref "X3")
      (value "SSW-102-02-S-S")
      (footprint "eagle-import:SSW-102-02-S-S")
      (libsource (lib "eagle-import") (part "SSW-102-02-S-S"))
    )
    (comp (ref "ZD2")
      (value "13V")
      (footprint "eagle-import:MINIMELF")
      (libsource (lib "eagle-import") (part "ZENER-DIODEMINIMELF"))
    )
    (comp (ref "ZD3")
      (value "6V2")
      (footprint "eagle-import:MINIMELF")
      (libsource (lib "eagle-import") (part "ZENER-DIODEMINIMELF"))
    )
    (comp (ref "+5V")
      (value "735427-2")
      (footprint "eagle-import:PCB_SHIELD_TAB")
      (libsource (lib "eagle-import") (part "PCB_TEST_TABSHIELD"))
    )
    (comp (ref "C24")
      (value "2u2")
      (footprint "eagle-import:C0805")
      (libsource (lib "eagle-import") (part "C-EUC0805"))
    )
    (comp (ref "C25")
      (value "330n")
      (footprint "eagle-import:C0805")
      (libsource (lib "eagle-import") (part "C-EUC0805"))
    )
    (comp (ref "C26")
      (value "100n")
      (footprint "eagle-import:C0805")
      (libsource (lib "eagle-import") (part "C-EUC0805"))
    )
    (comp (ref "C27")
      (value "47u")
      (footprint "eagle-import:CAPAE660X610N")
      (libsource (lib "eagle-import") (part "ECAPPANASONIC_H"))
    )
    (comp (ref "C28")
      (value "22n")
      (footprint "eagle-import:C0805")
      (libsource (lib "eagle-import") (part "C-EUC0805"))
    )
    (comp (ref "C29")
      (value "100n")
      (footprint "eagle-import:C0805")
      (libsource (lib "eagle-import") (part "C-EUC0805"))
    )
    (comp (ref "C30")
      (value "2u2/100V")
      (footprint "eagle-import:C1210")
      (libsource (lib "eagle-import") (part "C-EUC1210"))
    )
    (comp (ref "C31")
      (value "330n")
      (footprint "eagle-import:C0805")
      (libsource (lib "eagle-import") (part "C-EUC0805"))
    )
    (comp (ref "C32")
      (value "330p")
      (footprint "eagle-import:C0805")
      (libsource (lib "eagle-import") (part "C-EUC0805"))
    )
    (comp (ref "C33")
      (value "10n")
      (footprint "eagle-import:C0805")
      (libsource (lib "eagle-import") (part "C-EUC0805"))
    )
    (comp (ref "C34")
      (value "47u")
      (footprint "eagle-import:CAPAE660X610N")
      (libsource (lib "eagle-import") (part "ECAPPANASONIC_H"))
    )
    (comp (ref "C35")
      (value "2u2")
      (footprint "eagle-import:C0805")
      (libsource (lib "eagle-import") (part "C-EUC0805"))
    )
    (comp (ref "C36")
      (value "100n")
      (footprint "eagle-import:C0805")
      (libsource (lib "eagle-import") (part "C-EUC0805"))
    )
    (comp (ref "C37")
      (value "2u2")
      (footprint "eagle-import:C0805")
      (libsource (lib "eagle-import") (part "C-EUC0805"))
    )
    (comp (ref "C38")
      (value "2u2")
      (footprint "eagle-import:C0805")
      (libsource (lib "eagle-import") (part "C-EUC0805"))
    )
    (comp (ref "C39")
      (value "3n3")
      (footprint "eagle-import:C0805")
      (libsource (lib "eagle-import") (part "C-EUC0805"))
    )
    (comp (ref "C40")
      (value "1n")
      (footprint "eagle-import:C0805")
      (libsource (lib "eagle-import") (part "C-EUC0805"))
    )
    (comp (ref "C41")
      (value "100n")
      (footprint "eagle-import:C0805")
      (libsource (lib "eagle-import") (part "C-EUC0805"))
    )
    (comp (ref "C42")
      (value "4u7")
      (footprint "eagle-import:EC1206")
      (libsource (lib "eagle-import") (part "ECAP1206"))
    )
    (comp (ref "D8")
      (value "DFLS1100-7")
      (footprint "eagle-import:SOD123")
      (libsource (lib "eagle-import") (part "SCHOTTKYSOD123"))
    )
    (comp (ref "D9")
      (value "SKL16")
      (footprint "eagle-import:SOD123")
      (libsource (lib "eagle-import") (part "SCHOTTKYSOD123"))
    )
    (comp (ref "D10")
      (value "SKL16")
      (footprint "eagle-import:SOD123")
      (libsource (lib "eagle-import") (part "SCHOTTKYSOD123"))
    )
    (comp (ref "D11")
      (value "DFLS1100-7")
      (footprint "eagle-import:SOD123")
      (libsource (lib "eagle-import") (part "SCHOTTKYSOD123"))
    )
    (comp (ref "FB")
      (value "60R@100MHz")
      (footprint "eagle-import:BEAD0603")
      (libsource (lib "eagle-import") (part "FERRITE_BEAD0603"))
    )
    (comp (ref "FB2")
      (value "60R@100MHz")
      (footprint "eagle-import:BEAD0603")
      (libsource (lib "eagle-import") (part "FERRITE_BEAD0603"))
    )
    (comp (ref "FB3")
      (value "60R@100MHz")
      (footprint "eagle-import:BEAD0603")
      (libsource (lib "eagle-import") (part "FERRITE_BEAD0603"))
    )
    (comp (ref "IC3")
      (value "MC79L05")
      (footprint "eagle-import:SOIC127P600X173-8N")
      (libsource (lib "eagle-import") (part "MC79LXXSOIC"))
    )
    (comp (ref "IC4")
      (value "MC78L05")
      (footprint "eagle-import:SOIC127P600X173-8N")
      (libsource (lib "eagle-import") (part "MC78LXXSOIC8"))
    )
    (comp (ref "IC5")
      (value "LM5574")
      (footprint "eagle-import:SOP65P640X110-16N")
      (fields (field (name "MPN") "LM5574MT"))
      (libsource (lib "eagle-import") (part "LM5574"))
    )
    (comp (ref "IC6")
      (value "LP2951SO8")
      (footprint "eagle-import:SOIC127P600X175-8N")
      (libsource (lib "eagle-import") (part "LP2951SO8"))
    )
    (comp (ref "L4")
      (value "2u2")
      (footprint "eagle-import:L1210")
      (libsource (lib "eagle-import") (part "L1210"))
    )
    (comp (ref "L5")
      (value "2u2")
      (footprint "eagle-import:L1210")
      (libsource (lib "eagle-import") (part "L1210"))
    )
    (comp (ref "L6")
      (value "2u2")
      (footprint "eagle-import:L1210")
      (libsource (lib "eagle-import") (part "L1210"))
    )
    (comp (ref "LED1")
      (value "HSMY-C170")
      (footprint "eagle-import:CHIPLED_0805")
      (libsource (lib "eagle-import") (part "LEDCHIPLED_0805"))
    )
    (comp (ref "R17")
      (value "39K")
      (footprint "eagle-import:R0805")
      (libsource (lib "eagle-import") (part "R-EU_R0805"))
    )
    (comp (ref "R18")
      (value "1K8")
      (footprint "eagle-import:R0805")
      (libsource (lib "eagle-import") (part "R-EU_R0805"))
    )
    (comp (ref "R19")
      (value "10R")
      (footprint "eagle-import:R1206")
      (libsource (lib "eagle-import") (part "R-EU_R1206"))
    )
    (comp (ref "R20")
      (value "30K")
      (footprint "eagle-import:R0805")
      (libsource (lib "eagle-import") (part "R-EU_R0805"))
    )
    (comp (ref "R21")
      (value "390R")
      (footprint "eagle-import:R0805")
      (libsource (lib "eagle-import") (part "R-EU_R0805"))
    )
    (comp (ref "R22")
      (value "22K")
      (footprint "eagle-import:R0805")
      (libsource (lib "eagle-import") (part "R-EU_R0805"))
    )
    (comp (ref "R23")
      (value "51K")
      (footprint "eagle-import:R0805")
      (libsource (lib "eagle-import") (part "R-EU_R0805"))
    )
    (comp (ref "R24")
      (value "12K")
      (footprint "eagle-import:R0805")
      (libsource (lib "eagle-import") (part "R-EU_R0805"))
    )
    (comp (ref "R25")
      (value "4K7")
      (footprint "eagle-import:R0805")
      (libsource (lib "eagle-import") (part "R-EU_R0805"))
    )
    (comp (ref "R26")
      (value "3K9")
      (footprint "eagle-import:R0805")
      (libsource (lib "eagle-import") (part "R-EU_R0805"))
    )
    (comp (ref "R27")
      (value "10K")
      (footprint "eagle-import:R0805")
      (libsource (lib "eagle-import") (part "R-EU_R0805"))
    )
    (comp (ref "TR1")
      (value "MSD1260-824")
      (footprint "eagle-import:MSD1260")
      (libsource (lib "eagle-import") (part "COILCRAFT_MSD1260INV"))
    )
    (comp (ref "C64")
      (value "100n")
      (footprint "eagle-import:C0603")
      (libsource (lib "eagle-import") (part "C-EUC0603"))
    )
    (comp (ref "C65")
      (value "100n")
      (footprint "eagle-import:C0603")
      (libsource (lib "eagle-import") (part "C-EUC0603"))
    )
    (comp (ref "C66")
      (value "100n")
      (footprint "eagle-import:C0603")
      (libsource (lib "eagle-import") (part "C-EUC0603"))
    )
    (comp (ref "C67")
      (value "10u")
      (footprint "eagle-import:C1206")
      (libsource (lib "eagle-import") (part "C-EUC1206"))
    )
    (comp (ref "C68")
      (value "10u")
      (footprint "eagle-import:EC1206")
      (libsource (lib "eagle-import") (part "ECAP1206"))
    )
    (comp (ref "C69")
      (value "1u")
      (footprint "eagle-import:C0805")
      (libsource (lib "eagle-import") (part "C-EUC0805"))
    )
    (comp (ref "C70")
      (value "100n")
      (footprint "eagle-import:C0603")
      (libsource (lib "eagle-import") (part "C-EUC0603"))
    )
    (comp (ref "C71")
      (value "1u")
      (footprint "eagle-import:C0805")
      (libsource (lib "eagle-import") (part "C-EUC0805"))
    )
    (comp (ref "C72")
      (value "100n")
      (footprint "eagle-import:C0603")
      (libsource (lib "eagle-import") (part "C-EUC0603"))
    )
    (comp (ref "C73")
      (value "1u")
      (footprint "eagle-import:C0805")
      (libsource (lib "eagle-import") (part "C-EUC0805"))
    )
    (comp (ref "IC10")
      (value "MCP23S08-E/SO")
      (footprint "eagle-import:SOIC127P1030X265-18N")
      (libsource (lib "eagle-import") (part "MCP23S08"))
    )
    (comp (ref "IC11")
      (value "DAC8552")
      (footprint "eagle-import:DGK8-M")
      (libsource (lib "eagle-import") (part "DAC8552_DGK_8M"))
    )
    (comp (ref "IC12")
      (value "REF5025")
      (footprint "eagle-import:SOIC127P600X175-8N")
      (libsource (lib "eagle-import") (part "REF50XX"))
    )
    (comp (ref "IC13")
      (value "ADS1120")
      (footprint "eagle-import:PW(R-PDSO-G16)")
      (libsource (lib "eagle-import") (part "ADS1120TSSOP-16"))
    )
    (comp (ref "JMP2")
      (value "0R-JMP41-2,3-4")
      (footprint "eagle-import:0R-JMP4")
      (libsource (lib "eagle-import") (part "0R-JMP41-2,3-4"))
    )
    (comp (ref "OE")
      (value "735427-2")
      (footprint "eagle-import:PCB_SHIELD_TAB")
      (libsource (lib "eagle-import") (part "PCB_TEST_TABSHIELD"))
    )
    (comp (ref "Q14")
      (value "BSS84P")
      (footprint "eagle-import:SOT95P237X112-3N")
      (fields (field (name "MPN") "IRLML2246TRPBF"))
      (libsource (lib "eagle-import") (part "IRLML2246TRPBF"))
    )
    (comp (ref "Q15")
      (value "2N7002")
      (footprint "eagle-import:SOT103P240X110-3N")
      (fields
        (field (name "MPN") "2N7002-7-F")
        (field (name "MPN_1") "2N7002-7-F")
        (field (name "OC_FARNELL") "1713823")
        (field (name "OC_NEWARK") "25R5679")
        (field (name "PACKAGE") "SOT-23-3")
        (field (name "SUPPLIER") "DIODES INC.")
      )
      (libsource (lib "eagle-import") (part "2N7002"))
    )
    (comp (ref "R73")
      (value "100K")
      (footprint "eagle-import:R0805")
      (libsource (lib "eagle-import") (part "R-EU_R0805"))
    )
    (comp (ref "R74")
      (value "10K")
      (footprint "eagle-import:R0805")
      (libsource (lib "eagle-import") (part "R-EU_R0805"))
    )
    (comp (ref "R75")
      (value "100K")
      (footprint "eagle-import:R0805")
      (libsource (lib "eagle-import") (part "R-EU_R0805"))
    )
    (comp (ref "R76")
      (value "10R")
      (footprint "eagle-import:R0805")
      (libsource (lib "eagle-import") (part "R-EU_R0805"))
    )
  )
  (nets
    (net (code "1") (name "+5V") (class "Default")
      (node (ref "C23") (pin "1") (pinfunction "1_1") (pintype "passive"))
      (node (ref "C64") (pin "1") (pinfunction "1_1") (pintype "passive"))
      (node (ref "C65") (pin "2") (pinfunction "2_2") (pintype "passive"))
      (node (ref "C67") (pin "1") (pinfunction "1_1") (pintype "passive"))
      (node (ref "C70") (pin "2") (pinfunction "2_2") (pintype "passive"))
      (node (ref "C71") (pin "2") (pinfunction "2_2") (pintype "passive"))
      (node (ref "FB3") (pin "P$2") (pinfunction "2_P$2") (pintype "passive"))
      (node (ref "IC10") (pin "18") (pinfunction "VDD_18") (pintype "power_in"))
      (node (ref "IC11") (pin "1") (pinfunction "VDD_1") (pintype "power_in"))
      (node (ref "IC12") (pin "2") (pinfunction "VIN_2") (pintype "passive"))
      (node (ref "IC13") (pin "13") (pinfunction "DVDD_13") (pintype "power_in"))
      (node (ref "IC2") (pin "1") (pinfunction "VDD1_1") (pintype "power_in"))
      (node (ref "Q13") (pin "B") (pinfunction "B_B") (pintype "passive"))
      (node (ref "Q14") (pin "2") (pinfunction "S_2") (pintype "passive"))
      (node (ref "R73") (pin "1") (pinfunction "1_1") (pintype "passive"))
      (node (ref "R76") (pin "1") (pinfunction "1_1") (pintype "passive"))
      (node (ref "R80") (pin "2") (pinfunction "2_2") (pintype "passive"))
      (node (ref "R85") (pin "2") (pinfunction "2_2") (pintype "passive"))
      (node (ref "X2") (pin "6") (pinfunction "1_6") (pintype "passive"))
      (node (ref "X4") (pin "2") (pinfunction "1_2") (pintype "passive"))
    )
    (net (code "2") (name "+VREF") (class "Default")
      (node (ref "C66") (pin "2") (pinfunction "2_2") (pintype "passive"))
      (node (ref "C68") (pin "+") (pinfunction "+_+") (pintype "passive"))
      (node (ref "IC11") (pin "2") (pinfunction "VREF_2") (pintype "input"))
      (node (ref "IC12") (pin "6") (pinfunction "VOUT_6") (pintype "output"))
      (node (ref "IC13") (pin "9") (pinfunction "REFP0_9") (pintype "input"))
      (node (ref "X5") (pin "7") (pinfunction "1_7") (pintype "passive"))
      (node (ref "X5") (pin "8") (pinfunction "1_8") (pintype "passive"))
    )
    (net (code "3") (name "-9V") (class "Default")
      (node (ref "C25") (pin "2") (pinfunction "2_2") (pintype "passive"))
      (node (ref "C27") (pin "2") (pinfunction "-_2") (pintype "passive"))
      (node (ref "IC3") (pin "2") (pinfunction "IN_2") (pintype "input"))
      (node (ref "IC3") (pin "3") (pinfunction "IN_3") (pintype "input"))
      (node (ref "IC3") (pin "6") (pinfunction "IN_6") (pintype "input"))
      (node (ref "IC3") (pin "7") (pinfunction "IN_7") (pintype "input"))
      (node (ref "L4") (pin "2") (pinfunction "2_2") (pintype "passive"))
      (node (ref "R39") (pin "2") (pinfunction "2_2") (pintype "passive"))
      (node (ref "R40") (pin "2") (pinfunction "2_2") (pintype "passive"))
    )
    (net (code "4") (name "AUX_USET_IN") (class "Default")
      (node (ref "R78") (pin "2") (pinfunction "2_2") (pintype "passive"))
      (node (ref "X4") (pin "11") (pinfunction "1_11") (pintype "passive"))
    )
    (net (code "5") (name "AUX_USET_SW") (class "Default")
      (node (ref "IC10") (pin "14") (pinfunction "GP4_14") (pintype "bidirectional"))
      (node (ref "IC15") (pin "1") (pinfunction "IN_1") (pintype "input"))
    )
    (net (code "6") (name "CC_ACTIVE") (class "Default")
      (node (ref "C77") (pin "1") (pinfunction "1_1") (pintype "passive"))
      (node (ref "IC10") (pin "12") (pinfunction "GP2_12") (pintype "bidirectional"))
      (node (ref "R85") (pin "1") (pinfunction "1_1") (pintype "passive"))
      (node (ref "R87") (pin "2") (pinfunction "2_2") (pintype "passive"))
    )
    (net (code "7") (name "CS_ADC") (class "Default")
      (node (ref "IC13") (pin "2") (pinfunction "~{CS}_2") (pintype "input"))
      (node (ref "X4") (pin "6") (pinfunction "1_6") (pintype "passive"))
    )
    (net (code "8") (name "CS_DAC") (class "Default")
      (node (ref "IC11") (pin "5") (pinfunction "~{SYNC}_5") (pintype "input"))
      (node (ref "X4") (pin "4") (pinfunction "1_4") (pintype "passive"))
    )
    (net (code "9") (name "CS_EXPANDER") (class "Default")
      (node (ref "IC10") (pin "7") (pinfunction "~{CS}_7") (pintype "input"))
      (node (ref "X4") (pin "3") (pinfunction "1_3") (pintype "passive"))
    )
    (net (code "10") (name "CV_ACTIVE") (class "Default")
      (node (ref "C74") (pin "1") (pinfunction "1_1") (pintype "passive"))
      (node (ref "IC10") (pin "15") (pinfunction "GP5_15") (pintype "bidirectional"))
      (node (ref "R80") (pin "1") (pinfunction "1_1") (pintype "passive"))
      (node (ref "R82") (pin "2") (pinfunction "2_2") (pintype "passive"))
    )
    (net (code "11") (name "DC_OUT") (class "Default")
      (node (ref "C1") (pin "+") (pinfunction "+_+") (pintype "passive"))
      (node (ref "C2") (pin "+") (pinfunction "+_+") (pintype "passive"))
      (node (ref "C3") (pin "1") (pinfunction "1_1") (pintype "passive"))
      (node (ref "C4") (pin "1") (pinfunction "1_1") (pintype "passive"))
      (node (ref "C6") (pin "2") (pinfunction "2_2") (pintype "passive"))
      (node (ref "C7") (pin "1") (pinfunction "1_1") (pintype "passive"))
      (node (ref "C8") (pin "1") (pinfunction "1_1") (pintype "passive"))
      (node (ref "D2") (pin "3") (pinfunction "C_3") (pintype "passive"))
      (node (ref "D4") (pin "3") (pinfunction "C_3") (pintype "passive"))
      (node (ref "D5") (pin "A") (pinfunction "A_A") (pintype "passive"))
      (node (ref "IC1") (pin "11") (pinfunction "VIN_11") (pintype "passive"))
      (node (ref "L5") (pin "1") (pinfunction "1_1") (pintype "passive"))
      (node (ref "R1") (pin "1") (pinfunction "1_1") (pintype "passive"))
      (node (ref "R2") (pin "1") (pinfunction "1_1") (pintype "passive"))
    )
    (net (code "12") (name "GND") (class "Default")
      (node (ref "C1") (pin "-") (pinfunction "-_-") (pintype "passive"))
      (node (ref "C10") (pin "2") (pinfunction "2_2") (pintype "passive"))
      (node (ref "C16") (pin "-") (pinfunction "-_-") (pintype "passive"))
      (node (ref "C16") (pin "-.1") (pinfunction "-_-.1") (pintype "passive"))
      (node (ref "C18") (pin "2") (pinfunction "2_2") (pintype "passive"))
      (node (ref "C2") (pin "-") (pinfunction "-_-") (pintype "passive"))
      (node (ref "C23") (pin "2") (pinfunction "2_2") (pintype "passive"))
      (node (ref "C24") (pin "2") (pinfunction "2_2") (pintype "passive"))
      (node (ref "C25") (pin "1") (pinfunction "1_1") (pintype "passive"))
      (node (ref "C26") (pin "1") (pinfunction "1_1") (pintype "passive"))
      (node (ref "C27") (pin "1") (pinfunction "+_1") (pintype "passive"))
      (node (ref "C29") (pin "2") (pinfunction "2_2") (pintype "passive"))
      (node (ref "C3") (pin "2") (pinfunction "2_2") (pintype "passive"))
      (node (ref "C30") (pin "2") (pinfunction "2_2") (pintype "passive"))
      (node (ref "C31") (pin "2") (pinfunction "2_2") (pintype "passive"))
      (node (ref "C33") (pin "2") (pinfunction "2_2") (pintype "passive"))
      (node (ref "C34") (pin "2") (pinfunction "-_2") (pintype "passive"))
      (node (ref "C35") (pin "2") (pinfunction "2_2") (pintype "passive"))
      (node (ref "C36") (pin "1") (pinfunction "1_1") (pintype "passive"))
      (node (ref "C37") (pin "2") (pinfunction "2_2") (pintype "passive"))
      (node (ref "C38") (pin "2") (pinfunction "2_2") (pintype "passive"))
      (node (ref "C39") (pin "1") (pinfunction "1_1") (pintype "passive"))
      (node (ref "C4") (pin "2") (pinfunction "2_2") (pintype "passive"))
      (node (ref "C41") (pin "2") (pinfunction "2_2") (pintype "passive"))
      (node (ref "C42") (pin "-") (pinfunction "-_-") (pintype "passive"))
      (node (ref "C43") (pin "2") (pinfunction "2_2") (pintype "passive"))
      (node (ref "C44") (pin "2") (pinfunction "2_2") (pintype "passive"))
      (node (ref "C5") (pin "-") (pinfunction "-_-") (pintype "passive"))
      (node (ref "C5") (pin "-.1") (pinfunction "-_-.1") (pintype "passive"))
      (node (ref "C52") (pin "1") (pinfunction "1_1") (pintype "passive"))
      (node (ref "C53") (pin "2") (pinfunction "2_2") (pintype "passive"))
      (node (ref "C54") (pin "1") (pinfunction "1_1") (pintype "passive"))
      (node (ref "C55") (pin "1") (pinfunction "1_1") (pintype "passive"))
      (node (ref "C56") (pin "1") (pinfunction "1_1") (pintype "passive"))
      (node (ref "C57") (pin "1") (pinfunction "1_1") (pintype "passive"))
      (node (ref "C58") (pin "1") (pinfunction "1_1") (pintype "passive"))
      (node (ref "C59") (pin "2") (pinfunction "2_2") (pintype "passive"))
      (node (ref "C60") (pin "1") (pinfunction "1_1") (pintype "passive"))
      (node (ref "C61") (pin "1") (pinfunction "1_1") (pintype "passive"))
      (node (ref "C64") (pin "2") (pinfunction "2_2") (pintype "passive"))
      (node (ref "C65") (pin "1") (pinfunction "1_1") (pintype "passive"))
      (node (ref "C66") (pin "1") (pinfunction "1_1") (pintype "passive"))
      (node (ref "C67") (pin "2") (pinfunction "2_2") (pintype "passive"))
      (node (ref "C68") (pin "-") (pinfunction "-_-") (pintype "passive"))
      (node (ref "C69") (pin "2") (pinfunction "2_2") (pintype "passive"))
      (node (ref "C7") (pin "2") (pinfunction "2_2") (pintype "passive"))
      (node (ref "C70") (pin "1") (pinfunction "1_1") (pintype "passive"))
      (node (ref "C71") (pin "1") (pinfunction "1_1") (pintype "passive"))
      (node (ref "C72") (pin "1") (pinfunction "1_1") (pintype "passive"))
      (node (ref "C73") (pin "1") (pinfunction "1_1") (pintype "passive"))
      (node (ref "C74") (pin "2") (pinfunction "2_2") (pintype "passive"))
      (node (ref "C75") (pin "1") (pinfunction "1_1") (pintype "passive"))
      (node (ref "C76") (pin "1") (pinfunction "1_1") (pintype "passive"))
      (node (ref "C77") (pin "2") (pinfunction "2_2") (pintype "passive"))
      (node (ref "D1") (pin "1") (pinfunction "A1_1") (pintype "passive"))
      (node (ref "D1") (pin "2") (pinfunction "A2_2") (pintype "passive"))
      (node (ref "D10") (pin "A") (pinfunction "A_A") (pintype "passive"))
      (node (ref "D3") (pin "1") (pinfunction "A1_1") (pintype "passive"))
      (node (ref "D3") (pin "2") (pinfunction "A2_2") (pintype "passive"))
      (node (ref "D6") (pin "1") (pinfunction "A_1") (pintype "passive"))
      (node (ref "D6") (pin "2") (pinfunction "A_2") (pintype "passive"))
      (node (ref "D9") (pin "C") (pinfunction "C_C") (pintype "passive"))
      (node (ref "IC1") (pin "TP") (pinfunction "PGND_TP") (pintype "passive"))
      (node (ref "IC10") (pin "4") (pinfunction "A1_4") (pintype "input"))
      (node (ref "IC10") (pin "5") (pinfunction "A0_5") (pintype "input"))
      (node (ref "IC10") (pin "9") (pinfunction "VSS_9") (pintype "power_in"))
      (node (ref "IC11") (pin "8") (pinfunction "GND_8") (pintype "power_in"))
      (node (ref "IC12") (pin "4") (pinfunction "GND_4") (pintype "passive"))
      (node (ref "IC13") (pin "3") (pinfunction "CLK_3") (pintype "bidirectional"))
      (node (ref "IC13") (pin "4") (pinfunction "DGND_4") (pintype "power_in"))
      (node (ref "IC13") (pin "5") (pinfunction "AVSS_5") (pintype "power_in"))
      (node (ref "IC13") (pin "8") (pinfunction "REFN0_8") (pintype "input"))
      (node (ref "IC15") (pin "3") (pinfunction "GND_3") (pintype "passive"))
      (node (ref "IC2") (pin "4") (pinfunction "GND1_4") (pintype "power_in"))
      (node (ref "IC3") (pin "5") (pinfunction "GND_5") (pintype "passive"))
      (node (ref "IC4") (pin "2") (pinfunction "GND_2") (pintype "passive"))
      (node (ref "IC4") (pin "3") (pinfunction "GND_3") (pintype "passive"))
      (node (ref "IC4") (pin "6") (pinfunction "GND_6") (pintype "passive"))
      (node (ref "IC4") (pin "7") (pinfunction "GND_7") (pintype "passive"))
      (node (ref "IC5") (pin "12") (pinfunction "PGND_12") (pintype "passive"))
      (node (ref "IC5") (pin "9") (pinfunction "AGND_9") (pintype "passive"))
      (node (ref "IC6") (pin "4") (pinfunction "GND_4") (pintype "passive"))
      (node (ref "IC8") (pin "5") (pinfunction "+IN_5") (pintype "input"))
      (node (ref "Q15") (pin "2") (pinfunction "S_2") (pintype "passive"))
      (node (ref "Q8") (pin "2") (pinfunction "D_2") (pintype "passive"))
      (node (ref "R1") (pin "2") (pinfunction "2_2") (pintype "passive"))
      (node (ref "R18") (pin "1") (pinfunction "1_1") (pintype "passive"))
      (node (ref "R21") (pin "2") (pinfunction "2_2") (pintype "passive"))
      (node (ref "R22") (pin "2") (pinfunction "2_2") (pintype "passive"))
      (node (ref "R25") (pin "2") (pinfunction "2_2") (pintype "passive"))
      (node (ref "R26") (pin "2") (pinfunction "2_2") (pintype "passive"))
      (node (ref "R42") (pin "1") (pinfunction "1_1") (pintype "passive"))
      (node (ref "R44") (pin "1") (pinfunction "1_1") (pintype "passive"))
      (node (ref "R48") (pin "1") (pinfunction "1_1") (pintype "passive"))
      (node (ref "R60") (pin "1") (pinfunction "1_1") (pintype "passive"))
      (node (ref "R75") (pin "1") (pinfunction "1_1") (pintype "passive"))
      (node (ref "R83") (pin "1") (pinfunction "1_1") (pintype "passive"))
      (node (ref "R84") (pin "2") (pinfunction "2_2") (pintype "passive"))
      (node (ref "R9") (pin "1") (pinfunction "1_1") (pintype "passive"))
      (node (ref "SH1") (pin "2") (pinfunction "GND_B_2") (pintype "bidirectional"))
      (node (ref "SH2") (pin "2") (pinfunction "GND_B_2") (pintype "bidirectional"))
      (node (ref "TR1") (pin "4") (pinfunction "4_4") (pintype "passive"))
      (node (ref "X2") (pin "2") (pinfunction "1_2") (pintype "passive"))
      (node (ref "X4") (pin "10") (pinfunction "1_10") (pintype "passive"))
      (node (ref "X4") (pin "12") (pinfunction "1_12") (pintype "passive"))
      (node (ref "X4") (pin "14") (pinfunction "1_14") (pintype "passive"))
      (node (ref "X4") (pin "16") (pinfunction "1_16") (pintype "passive"))
      (node (ref "X5") (pin "5") (pinfunction "1_5") (pintype "passive"))
      (node (ref "X5") (pin "6") (pinfunction "1_6") (pintype "passive"))
    )
    (net (code "13") (name "I_MON") (class "Default")
      (node (ref "IC13") (pin "7") (pinfunction "AIN2_7") (pintype "input"))
      (node (ref "IC9") (pin "6") (pinfunction "OUT_6") (pintype "output"))
      (node (ref "R65") (pin "1") (pinfunction "1_1") (pintype "passive"))
      (node (ref "R69") (pin "2") (pinfunction "2_2") (pintype "passive"))
    )
    (net (code "14") (name "I_SERVO") (class "Default")
      (node (ref "C62") (pin "2") (pinfunction "2_2") (pintype "passive"))
      (node (ref "CC") (pin "1") (pinfunction "P$1_1") (pintype "bidirectional"))
      (node (ref "D18") (pin "C") (pinfunction "C_C") (pintype "passive"))
      (node (ref "D19") (pin "A") (pinfunction "A_A") (pintype "passive"))
      (node (ref "IC8") (pin "1") (pinfunction "OUT_1") (pintype "output"))
      (node (ref "R88") (pin "1") (pinfunction "1_1") (pintype "passive"))
    )
    (net (code "15") (name "I_SET") (class "Default")
      (node (ref "R62") (pin "1") (pinfunction "1_1") (pintype "passive"))
      (node (ref "X5") (pin "4") (pinfunction "1_4") (pintype "passive"))
    )
    (net (code "16") (name "I_SET_IN") (class "Default")
      (node (ref "IC11") (pin "3") (pinfunction "VOUTB_3") (pintype "output"))
      (node (ref "IC13") (pin "6") (pinfunction "AIN3/REFN1_6") (pintype "input"))
      (node (ref "X5") (pin "2") (pinfunction "1_2") (pintype "passive"))
    )
    (net (code "17") (name "MCU_VCC") (class "Default")
      (node (ref "X3") (pin "2") (pinfunction "1_2") (pintype "passive"))
      (node (ref "X4") (pin "15") (pinfunction "1_15") (pintype "passive"))
    )
    (net (code "18") (name "Net-(+5V-P$1)") (class "Default")
      (node (ref "+5V") (pin "1") (pinfunction "P$1_1") (pintype "bidirectional"))
      (node (ref "C42") (pin "+") (pinfunction "+_+") (pintype "passive"))
      (node (ref "FB3") (pin "P$1") (pinfunction "1_P$1") (pintype "passive"))
      (node (ref "IC6") (pin "1") (pinfunction "OUT_1") (pintype "output"))
      (node (ref "R24") (pin "1") (pinfunction "1_1") (pintype "passive"))
      (node (ref "R27") (pin "1") (pinfunction "1_1") (pintype "passive"))
    )
    (net (code "19") (name "Net-(C10-Pad1)") (class "Default")
      (node (ref "C10") (pin "1") (pinfunction "1_1") (pintype "passive"))
      (node (ref "C16") (pin "+") (pinfunction "+_+") (pintype "passive"))
      (node (ref "C16") (pin "+.1") (pinfunction "+_+.1") (pintype "passive"))
      (node (ref "C18") (pin "1") (pinfunction "1_1") (pintype "passive"))
      (node (ref "C20") (pin "1") (pinfunction "1_1") (pintype "passive"))
      (node (ref "L1") (pin "2") (pinfunction "2_2") (pintype "passive"))
      (node (ref "L2") (pin "1") (pinfunction "1_1") (pintype "passive"))
      (node (ref "R11") (pin "1") (pinfunction "1_1") (pintype "passive"))
      (node (ref "R12") (pin "1") (pinfunction "1_1") (pintype "passive"))
      (node (ref "R13") (pin "1") (pinfunction "1_1") (pintype "passive"))
    )
    (net (code "20") (name "Net-(C11-Pad1)") (class "Default")
      (node (ref "C11") (pin "1") (pinfunction "1_1") (pintype "passive"))
      (node (ref "C17") (pin "2") (pinfunction "2_2") (pintype "passive"))
      (node (ref "L2") (pin "2") (pinfunction "2_2") (pintype "passive"))
      (node (ref "L3") (pin "1") (pinfunction "1_1") (pintype "passive"))
      (node (ref "R8") (pin "1") (pinfunction "1_1") (pintype "passive"))
    )
    (net (code "21") (name "Net-(C12-Pad1)") (class "Default")
      (node (ref "C12") (pin "1") (pinfunction "1_1") (pintype "passive"))
      (node (ref "C13") (pin "1") (pinfunction "1_1") (pintype "passive"))
      (node (ref "C14") (pin "1") (pinfunction "1_1") (pintype "passive"))
      (node (ref "FB1") (pin "1") (pinfunction "1_1") (pintype "passive"))
      (node (ref "L3") (pin "2") (pinfunction "2_2") (pintype "passive"))
      (node (ref "R8") (pin "2") (pinfunction "2_2") (pintype "passive"))
    )
    (net (code "22") (name "Net-(C15-Pad2)") (class "Default")
      (node (ref "C15") (pin "2") (pinfunction "2_2") (pintype "passive"))
      (node (ref "R9") (pin "2") (pinfunction "2_2") (pintype "passive"))
    )
    (net (code "23") (name "Net-(C20-Pad2)") (class "Default")
      (node (ref "C20") (pin "2") (pinfunction "2_2") (pintype "passive"))
      (node (ref "R14") (pin "2") (pinfunction "2_2") (pintype "passive"))
    )
    (net (code "24") (name "Net-(C21-Pad1)") (class "Default")
      (node (ref "C21") (pin "1") (pinfunction "1_1") (pintype "passive"))
      (node (ref "R10") (pin "1") (pinfunction "1_1") (pintype "passive"))
    )
    (net (code "25") (name "Net-(C24-Pad1)") (class "Default")
      (node (ref "C24") (pin "1") (pinfunction "1_1") (pintype "passive"))
      (node (ref "D8") (pin "A") (pinfunction "A_A") (pintype "passive"))
      (node (ref "L4") (pin "1") (pinfunction "1_1") (pintype "passive"))
    )
    (net (code "26") (name "Net-(C32-Pad2)") (class "Default")
      (node (ref "C32") (pin "2") (pinfunction "2_2") (pintype "passive"))
      (node (ref "R19") (pin "2") (pinfunction "2_2") (pintype "passive"))
    )
    (net (code "27") (name "Net-(C34-+)") (class "Default")
      (node (ref "C34") (pin "1") (pinfunction "+_1") (pintype "passive"))
      (node (ref "C37") (pin "1") (pinfunction "1_1") (pintype "passive"))
      (node (ref "C38") (pin "1") (pinfunction "1_1") (pintype "passive"))
      (node (ref "IC5") (pin "11") (pinfunction "OUT_11") (pintype "output"))
      (node (ref "L6") (pin "1") (pinfunction "1_1") (pintype "passive"))
      (node (ref "R20") (pin "1") (pinfunction "1_1") (pintype "passive"))
      (node (ref "TR1") (pin "3") (pinfunction "3_3") (pintype "passive"))
    )
    (net (code "28") (name "Net-(C40-Pad2)") (class "Default")
      (node (ref "C40") (pin "2") (pinfunction "2_2") (pintype "passive"))
      (node (ref "R23") (pin "2") (pinfunction "2_2") (pintype "passive"))
    )
    (net (code "29") (name "Net-(C44-Pad1)") (class "Default")
      (node (ref "C44") (pin "1") (pinfunction "1_1") (pintype "passive"))
      (node (ref "R38") (pin "1") (pinfunction "1_1") (pintype "passive"))
    )
    (net (code "30") (name "Net-(C45-Pad2)") (class "Default")
      (node (ref "C45") (pin "2") (pinfunction "2_2") (pintype "passive"))
      (node (ref "R43") (pin "1") (pinfunction "1_1") (pintype "passive"))
    )
    (net (code "31") (name "Net-(C46-Pad2)") (class "Default")
      (node (ref "C46") (pin "2") (pinfunction "2_2") (pintype "passive"))
      (node (ref "R45") (pin "1") (pinfunction "1_1") (pintype "passive"))
    )
    (net (code "32") (name "Net-(C47-Pad1)") (class "Default")
      (node (ref "C47") (pin "1") (pinfunction "1_1") (pintype "passive"))
      (node (ref "R46") (pin "2") (pinfunction "2_2") (pintype "passive"))
      (node (ref "R47") (pin "1") (pinfunction "1_1") (pintype "passive"))
    )
    (net (code "33") (name "Net-(C48-Pad1)") (class "Default")
      (node (ref "C48") (pin "1") (pinfunction "1_1") (pintype "passive"))
      (node (ref "R56") (pin "2") (pinfunction "2_2") (pintype "passive"))
      (node (ref "R57") (pin "1") (pinfunction "1_1") (pintype "passive"))
    )
    (net (code "34") (name "Net-(C49-Pad2)") (class "Default")
      (node (ref "C49") (pin "2") (pinfunction "2_2") (pintype "passive"))
      (node (ref "R54") (pin "1") (pinfunction "1_1") (pintype "passive"))
    )
    (net (code "35") (name "Net-(C50-Pad2)") (class "Default")
      (node (ref "C50") (pin "2") (pinfunction "2_2") (pintype "passive"))
      (node (ref "R55") (pin "1") (pinfunction "1_1") (pintype "passive"))
    )
    (net (code "36") (name "Net-(C51-Pad2)") (class "Default")
      (node (ref "C51") (pin "2") (pinfunction "2_2") (pintype "passive"))
      (node (ref "R58") (pin "1") (pinfunction "1_1") (pintype "passive"))
    )
    (net (code "37") (name "Net-(C62-Pad1)") (class "Default")
      (node (ref "C62") (pin "1") (pinfunction "1_1") (pintype "passive"))
      (node (ref "R71") (pin "1") (pinfunction "1_1") (pintype "passive"))
    )
    (net (code "38") (name "Net-(C63-Pad2)") (class "Default")
      (node (ref "C63") (pin "2") (pinfunction "2_2") (pintype "passive"))
      (node (ref "R72") (pin "1") (pinfunction "1_1") (pintype "passive"))
    )
    (net (code "39") (name "Net-(D1-C)") (class "Default")
      (node (ref "D1") (pin "3") (pinfunction "C_3") (pintype "passive"))
      (node (ref "D2") (pin "1") (pinfunction "A1_1") (pintype "passive"))
      (node (ref "D2") (pin "2") (pinfunction "A2_2") (pintype "passive"))
      (node (ref "X1") (pin "1") (pinfunction "1_1") (pintype "bidirectional"))
    )
    (net (code "40") (name "Net-(D3-C)") (class "Default")
      (node (ref "D3") (pin "3") (pinfunction "C_3") (pintype "passive"))
      (node (ref "D4") (pin "1") (pinfunction "A1_1") (pintype "passive"))
      (node (ref "D4") (pin "2") (pinfunction "A2_2") (pintype "passive"))
      (node (ref "X1") (pin "2") (pinfunction "1_2") (pintype "bidirectional"))
    )
    (net (code "41") (name "Net-(D6-C)") (class "Default")
      (node (ref "C15") (pin "1") (pinfunction "1_1") (pintype "passive"))
      (node (ref "D6") (pin "3") (pinfunction "C_3") (pintype "passive"))
      (node (ref "L1") (pin "1") (pinfunction "1_1") (pintype "passive"))
      (node (ref "Q1") (pin "2") (pinfunction "D_2") (pintype "passive"))
    )
    (net (code "42") (name "Net-(D7-PadA)") (class "Default")
      (node (ref "D7") (pin "A") (pinfunction "A_A") (pintype "passive"))
      (node (ref "Q2") (pin "B") (pinfunction "B_B") (pintype "passive"))
      (node (ref "R12") (pin "2") (pinfunction "2_2") (pintype "passive"))
      (node (ref "R15") (pin "1") (pinfunction "1_1") (pintype "passive"))
    )
    (net (code "43") (name "Net-(D7-PadC)") (class "Default")
      (node (ref "D7") (pin "C") (pinfunction "C_C") (pintype "passive"))
      (node (ref "Q2") (pin "E") (pinfunction "E_E") (pintype "passive"))
      (node (ref "R11") (pin "2") (pinfunction "2_2") (pintype "passive"))
    )
    (net (code "44") (name "Net-(D8-PadC)") (class "Default")
      (node (ref "D8") (pin "C") (pinfunction "C_C") (pintype "passive"))
      (node (ref "TR1") (pin "2") (pinfunction "2_2") (pintype "passive"))
    )
    (net (code "45") (name "Net-(D12-PadC)") (class "Default")
      (node (ref "D12") (pin "C") (pinfunction "C_C") (pintype "passive"))
      (node (ref "D13") (pin "A") (pinfunction "A_A") (pintype "passive"))
      (node (ref "Q4") (pin "G") (pinfunction "G_G") (pintype "passive"))
      (node (ref "R30") (pin "1") (pinfunction "1_1") (pintype "passive"))
    )
    (net (code "46") (name "Net-(D13-PadC)") (class "Default")
      (node (ref "D13") (pin "C") (pinfunction "C_C") (pintype "passive"))
      (node (ref "ZD3") (pin "C") (pinfunction "C_C") (pintype "passive"))
    )
    (net (code "47") (name "Net-(D14-PadC)") (class "Default")
      (node (ref "D14") (pin "C") (pinfunction "C_C") (pintype "passive"))
      (node (ref "Q9") (pin "2") (pinfunction "C_2") (pintype "passive"))
      (node (ref "Q9") (pin "4") (pinfunction "C_4") (pintype "passive"))
      (node (ref "ZD3") (pin "A") (pinfunction "A_A") (pintype "passive"))
    )
    (net (code "48") (name "Net-(D15-PadC)") (class "Default")
      (node (ref "D15") (pin "C") (pinfunction "C_C") (pintype "passive"))
      (node (ref "Q6") (pin "C") (pinfunction "C_C") (pintype "passive"))
      (node (ref "ZD2") (pin "C") (pinfunction "C_C") (pintype "passive"))
    )
    (net (code "49") (name "Net-(D16-PadA)") (class "Default")
      (node (ref "D16") (pin "A") (pinfunction "A_A") (pintype "passive"))
      (node (ref "D18") (pin "A") (pinfunction "A_A") (pintype "passive"))
      (node (ref "R50") (pin "1") (pinfunction "1_1") (pintype "passive"))
    )
    (net (code "50") (name "Net-(FB-1)") (class "Default")
      (node (ref "C26") (pin "2") (pinfunction "2_2") (pintype "passive"))
      (node (ref "D9") (pin "A") (pinfunction "A_A") (pintype "passive"))
      (node (ref "FB") (pin "P$1") (pinfunction "1_P$1") (pintype "passive"))
      (node (ref "IC3") (pin "1") (pinfunction "OUT_1") (pintype "passive"))
    )
    (net (code "51") (name "Net-(FB2-1)") (class "Default")
      (node (ref "C29") (pin "1") (pinfunction "1_1") (pintype "passive"))
      (node (ref "D10") (pin "C") (pinfunction "C_C") (pintype "passive"))
      (node (ref "FB2") (pin "P$1") (pinfunction "1_P$1") (pintype "passive"))
      (node (ref "IC4") (pin "1") (pinfunction "VO_1") (pintype "passive"))
    )
    (net (code "52") (name "Net-(IC1-CAP)") (class "Default")
      (node (ref "C6") (pin "1") (pinfunction "1_1") (pintype "passive"))
      (node (ref "IC1") (pin "9") (pinfunction "CAP_9") (pintype "passive"))
    )
    (net (code "53") (name "Net-(IC1-FREQ)") (class "Default")
      (node (ref "IC1") (pin "2") (pinfunction "FREQ_2") (pintype "input"))
      (node (ref "R5") (pin "1") (pinfunction "1_1") (pintype "passive"))
    )
    (net (code "54") (name "Net-(IC1-GATE)") (class "Default")
      (node (ref "IC1") (pin "12") (pinfunction "GATE_12") (pintype "output"))
      (node (ref "R7") (pin "2") (pinfunction "2_2") (pintype "passive"))
    )
    (net (code "55") (name "Net-(IC1-ITH)") (class "Default")
      (node (ref "C19") (pin "1") (pinfunction "1_1") (pintype "passive"))
      (node (ref "IC1") (pin "6") (pinfunction "ITH_6") (pintype "bidirectional"))
      (node (ref "R10") (pin "2") (pinfunction "2_2") (pintype "passive"))
    )
    (net (code "56") (name "Net-(IC1-PLLIN{slash}MODE)") (class "Default")
      (node (ref "IC1") (pin "1") (pinfunction "PLLIN/MODE_1") (pintype "input"))
      (node (ref "JMP1") (pin "2") (pinfunction "2_2") (pintype "passive"))
    )
    (net (code "57") (name "Net-(IC1-RUN)") (class "Default")
      (node (ref "IC1") (pin "8") (pinfunction "RUN_8") (pintype "input"))
      (node (ref "R4") (pin "1") (pinfunction "1_1") (pintype "passive"))
    )
    (net (code "58") (name "Net-(IC1-SENSE)") (class "Default")
      (node (ref "C8") (pin "2") (pinfunction "2_2") (pintype "passive"))
      (node (ref "IC1") (pin "10") (pinfunction "SENSE_10") (pintype "input"))
      (node (ref "R3") (pin "2") (pinfunction "2_2") (pintype "passive"))
    )
    (net (code "59") (name "Net-(IC1-SS)") (class "Default")
      (node (ref "C9") (pin "2") (pinfunction "2_2") (pintype "passive"))
      (node (ref "IC1") (pin "4") (pinfunction "SS_4") (pintype "input"))
    )
    (net (code "60") (name "Net-(IC1-VFB)") (class "Default")
      (node (ref "IC1") (pin "5") (pinfunction "VFB_5") (pintype "input"))
      (node (ref "Q3") (pin "2") (pinfunction "S_2") (pintype "passive"))
      (node (ref "R13") (pin "2") (pinfunction "2_2") (pintype "passive"))
      (node (ref "R14") (pin "1") (pinfunction "1_1") (pintype "passive"))
      (node (ref "R16") (pin "1") (pinfunction "1_1") (pintype "passive"))
    )
    (net (code "61") (name "Net-(IC2-B1)") (class "Default")
      (node (ref "IC2") (pin "6") (pinfunction "B1_6") (pintype "output"))
      (node (ref "X2") (pin "3") (pinfunction "1_3") (pintype "passive"))
    )
    (net (code "62") (name "Net-(IC2-GND2)") (class "Default")
      (node (ref "C22") (pin "2") (pinfunction "2_2") (pintype "passive"))
      (node (ref "IC2") (pin "5") (pinfunction "GND2_5") (pintype "power_in"))
      (node (ref "X2") (pin "1") (pinfunction "1_1") (pintype "passive"))
    )
    (net (code "63") (name "Net-(IC2-VDD2)") (class "Default")
      (node (ref "C22") (pin "1") (pinfunction "1_1") (pintype "passive"))
      (node (ref "IC2") (pin "8") (pinfunction "VDD2_8") (pintype "power_in"))
      (node (ref "X2") (pin "5") (pinfunction "1_5") (pintype "passive"))
    )
    (net (code "64") (name "Net-(IC4-VI)") (class "Default")
      (node (ref "C31") (pin "1") (pinfunction "1_1") (pintype "passive"))
      (node (ref "C35") (pin "1") (pinfunction "1_1") (pintype "passive"))
      (node (ref "C41") (pin "1") (pinfunction "1_1") (pintype "passive"))
      (node (ref "IC4") (pin "8") (pinfunction "VI_8") (pintype "input"))
      (node (ref "IC6") (pin "8") (pinfunction "IN_8") (pintype "power_in"))
      (node (ref "L6") (pin "2") (pinfunction "2_2") (pintype "passive"))
      (node (ref "LED1") (pin "A") (pinfunction "A_A") (pintype "passive"))
    )
    (net (code "65") (name "Net-(IC5-BST)") (class "Default")
      (node (ref "C28") (pin "2") (pinfunction "2_2") (pintype "passive"))
      (node (ref "IC5") (pin "16") (pinfunction "BST_16") (pintype "input"))
    )
    (net (code "66") (name "Net-(IC5-COMP)") (class "Default")
      (node (ref "IC5") (pin "5") (pinfunction "COMP_5") (pintype "input"))
      (node (ref "R23") (pin "1") (pinfunction "1_1") (pintype "passive"))
    )
    (net (code "67") (name "Net-(IC5-FB)") (class "Default")
      (node (ref "C40") (pin "1") (pinfunction "1_1") (pintype "passive"))
      (node (ref "IC5") (pin "6") (pinfunction "FB_6") (pintype "input"))
      (node (ref "R20") (pin "2") (pinfunction "2_2") (pintype "passive"))
      (node (ref "R25") (pin "1") (pinfunction "1_1") (pintype "passive"))
    )
    (net (code "68") (name "Net-(IC5-IS)") (class "Default")
      (node (ref "D11") (pin "A") (pinfunction "A_A") (pintype "passive"))
      (node (ref "IC5") (pin "13") (pinfunction "IS_13") (pintype "input"))
      (node (ref "R19") (pin "1") (pinfunction "1_1") (pintype "passive"))
    )
    (net (code "69") (name "Net-(IC5-PRE)") (class "Default")
      (node (ref "C28") (pin "1") (pinfunction "1_1") (pintype "passive"))
      (node (ref "C32") (pin "1") (pinfunction "1_1") (pintype "passive"))
      (node (ref "D11") (pin "C") (pinfunction "C_C") (pintype "passive"))
      (node (ref "IC5") (pin "14") (pinfunction "SW_14") (pintype "output"))
      (node (ref "IC5") (pin "15") (pinfunction "PRE_15") (pintype "input"))
      (node (ref "TR1") (pin "1") (pinfunction "1_1") (pintype "passive"))
    )
    (net (code "70") (name "Net-(IC5-RAMP)") (class "Default")
      (node (ref "C39") (pin "2") (pinfunction "2_2") (pintype "passive"))
      (node (ref "IC5") (pin "8") (pinfunction "RAMP_8") (pintype "input"))
    )
    (net (code "71") (name "Net-(IC5-RT)") (class "Default")
      (node (ref "IC5") (pin "7") (pinfunction "RT_7") (pintype "input"))
      (node (ref "R22") (pin "1") (pinfunction "1_1") (pintype "passive"))
    )
    (net (code "72") (name "Net-(IC5-SD)") (class "Default")
      (node (ref "IC5") (pin "2") (pinfunction "SD_2") (pintype "input"))
      (node (ref "R17") (pin "1") (pinfunction "1_1") (pintype "passive"))
      (node (ref "R18") (pin "2") (pinfunction "2_2") (pintype "passive"))
    )
    (net (code "73") (name "Net-(IC5-SS)") (class "Default")
      (node (ref "C33") (pin "1") (pinfunction "1_1") (pintype "passive"))
      (node (ref "IC5") (pin "10") (pinfunction "SS_10") (pintype "input"))
    )
    (net (code "74") (name "Net-(IC5-VCC)") (class "Default")
      (node (ref "C36") (pin "2") (pinfunction "2_2") (pintype "passive"))
      (node (ref "IC5") (pin "1") (pinfunction "VCC_1") (pintype "power_in"))
    )
    (net (code "75") (name "Net-(IC5-VIN)") (class "Default")
      (node (ref "C30") (pin "1") (pinfunction "1_1") (pintype "passive"))
      (node (ref "IC5") (pin "3") (pinfunction "VIN_3") (pintype "input"))
      (node (ref "L5") (pin "2") (pinfunction "2_2") (pintype "passive"))
      (node (ref "R17") (pin "2") (pinfunction "2_2") (pintype "passive"))
    )
    (net (code "76") (name "Net-(IC6-FB)") (class "Default")
      (node (ref "IC6") (pin "7") (pinfunction "FB_7") (pintype "input"))
      (node (ref "R24") (pin "2") (pinfunction "2_2") (pintype "passive"))
      (node (ref "R26") (pin "1") (pinfunction "1_1") (pintype "passive"))
    )
    (net (code "77") (name "Net-(IC7A-+IN)") (class "Default")
      (node (ref "IC7") (pin "3") (pinfunction "+IN_3") (pintype "input"))
      (node (ref "R45") (pin "2") (pinfunction "2_2") (pintype "passive"))
      (node (ref "R49") (pin "2") (pinfunction "2_2") (pintype "passive"))
    )
    (net (code "78") (name "Net-(IC7A--IN)") (class "Default")
      (node (ref "C49") (pin "1") (pinfunction "1_1") (pintype "passive"))
      (node (ref "D17") (pin "C") (pinfunction "C_C") (pintype "passive"))
      (node (ref "IC7") (pin "2") (pinfunction "-IN_2") (pintype "input"))
      (node (ref "R51") (pin "2") (pinfunction "2_2") (pintype "passive"))
      (node (ref "R55") (pin "2") (pinfunction "2_2") (pintype "passive"))
    )
    (net (code "79") (name "Net-(IC7B-+IN)") (class "Default")
      (node (ref "IC7") (pin "5") (pinfunction "+IN_5") (pintype "input"))
      (node (ref "R42") (pin "2") (pinfunction "2_2") (pintype "passive"))
      (node (ref "R43") (pin "2") (pinfunction "2_2") (pintype "passive"))
      (node (ref "R46") (pin "1") (pinfunction "1_1") (pintype "passive"))
    )
    (net (code "80") (name "Net-(IC7B--IN)") (class "Default")
      (node (ref "IC7") (pin "6") (pinfunction "-IN_6") (pintype "input"))
      (node (ref "R52") (pin "2") (pinfunction "2_2") (pintype "passive"))
      (node (ref "R56") (pin "1") (pinfunction "1_1") (pintype "passive"))
      (node (ref "R58") (pin "2") (pinfunction "2_2") (pintype "passive"))
    )
    (net (code "81") (name "Net-(IC8A-+IN)") (class "Default")
      (node (ref "IC8") (pin "3") (pinfunction "+IN_3") (pintype "input"))
      (node (ref "R62") (pin "2") (pinfunction "2_2") (pintype "passive"))
    )
    (net (code "82") (name "Net-(IC8A--IN)") (class "Default")
      (node (ref "D19") (pin "C") (pinfunction "C_C") (pintype "passive"))
      (node (ref "IC8") (pin "2") (pinfunction "-IN_2") (pintype "input"))
      (node (ref "R65") (pin "2") (pinfunction "2_2") (pintype "passive"))
      (node (ref "R71") (pin "2") (pinfunction "2_2") (pintype "passive"))
      (node (ref "R72") (pin "2") (pinfunction "2_2") (pintype "passive"))
    )
    (net (code "83") (name "Net-(IC8B--IN)") (class "Default")
      (node (ref "IC8") (pin "6") (pinfunction "-IN_6") (pintype "input"))
      (node (ref "IC8") (pin "7") (pinfunction "OUT_7") (pintype "output"))
    )
    (net (code "84") (name "Net-(IC9A-+IN)") (class "Default")
      (node (ref "IC9") (pin "3") (pinfunction "+IN_3") (pintype "input"))
      (node (ref "R61") (pin "2") (pinfunction "2_2") (pintype "passive"))
      (node (ref "R63") (pin "2") (pinfunction "2_2") (pintype "passive"))
    )
    (net (code "85") (name "Net-(IC9A--IN)") (class "Default")
      (node (ref "IC9") (pin "2") (pinfunction "-IN_2") (pintype "input"))
      (node (ref "R67") (pin "2") (pinfunction "2_2") (pintype "passive"))
      (node (ref "R70") (pin "1") (pinfunction "1_1") (pintype "passive"))
    )
    (net (code "86") (name "Net-(IC10-GP0)") (class "Default")
      (node (ref "IC10") (pin "10") (pinfunction "GP0_10") (pintype "bidirectional"))
      (node (ref "JMP2") (pin "1") (pinfunction "1_1") (pintype "passive"))
    )
    (net (code "87") (name "Net-(IC10-INT)") (class "Default")
      (node (ref "IC10") (pin "8") (pinfunction "INT_8") (pintype "output"))
      (node (ref "JMP2") (pin "4") (pinfunction "4_4") (pintype "passive"))
    )
    (net (code "88") (name "Net-(IC12-TRIM{slash}NR)") (class "Default")
      (node (ref "C69") (pin "1") (pinfunction "1_1") (pintype "passive"))
      (node (ref "IC12") (pin "5") (pinfunction "TRIM/NR_5") (pintype "input"))
    )
    (net (code "89") (name "Net-(IC13-AVDD)") (class "Default")
      (node (ref "C72") (pin "2") (pinfunction "2_2") (pintype "passive"))
      (node (ref "C73") (pin "2") (pinfunction "2_2") (pintype "passive"))
      (node (ref "IC13") (pin "12") (pinfunction "AVDD_12") (pintype "power_in"))
      (node (ref "R76") (pin "2") (pinfunction "2_2") (pintype "passive"))
    )
    (net (code "90") (name "Net-(IC14-VD)") (class "Default")
      (node (ref "IC14") (pin "1") (pinfunction "VD_1") (pintype "bidirectional"))
      (node (ref "R78") (pin "1") (pinfunction "1_1") (pintype "passive"))
    )
    (net (code "91") (name "Net-(IC14-VS)") (class "Default")
      (node (ref "IC14") (pin "4") (pinfunction "VS_4") (pintype "bidirectional"))
      (node (ref "IC15") (pin "6") (pinfunction "S1_6") (pintype "bidirectional"))
    )
    (net (code "92") (name "Net-(IC16A-+IN)") (class "Default")
      (node (ref "IC16") (pin "7") (pinfunction "+IN_7") (pintype "input"))
      (node (ref "IC16") (pin "9") (pinfunction "+IN_9") (pintype "input"))
      (node (ref "R81") (pin "1") (pinfunction "1_1") (pintype "passive"))
      (node (ref "R83") (pin "2") (pinfunction "2_2") (pintype "passive"))
    )
    (net (code "93") (name "Net-(IC16A--IN)") (class "Default")
      (node (ref "IC16") (pin "5") (pinfunction "+IN_5") (pintype "input"))
      (node (ref "IC16") (pin "6") (pinfunction "-IN_6") (pintype "input"))
      (node (ref "R79") (pin "2") (pinfunction "2_2") (pintype "passive"))
    )
    (net (code "94") (name "Net-(IC16A-OUT)") (class "Default")
      (node (ref "IC16") (pin "1") (pinfunction "OUT_1") (pintype "open_collector"))
      (node (ref "IC16") (pin "2") (pinfunction "OUT_2") (pintype "open_collector"))
      (node (ref "R82") (pin "1") (pinfunction "1_1") (pintype "passive"))
    )
    (net (code "95") (name "Net-(IC16B--IN)") (class "Default")
      (node (ref "IC16") (pin "10") (pinfunction "-IN_10") (pintype "input"))
      (node (ref "IC16") (pin "4") (pinfunction "-IN_4") (pintype "input"))
      (node (ref "R84") (pin "1") (pinfunction "1_1") (pintype "passive"))
      (node (ref "R86") (pin "2") (pinfunction "2_2") (pintype "passive"))
    )
    (net (code "96") (name "Net-(IC16C--IN)") (class "Default")
      (node (ref "IC16") (pin "11") (pinfunction "+IN_11") (pintype "input"))
      (node (ref "IC16") (pin "8") (pinfunction "-IN_8") (pintype "input"))
      (node (ref "R88") (pin "2") (pinfunction "2_2") (pintype "passive"))
    )
    (net (code "97") (name "Net-(IC16C-OUT)") (class "Default")
      (node (ref "IC16") (pin "13") (pinfunction "OUT_13") (pintype "open_collector"))
      (node (ref "IC16") (pin "14") (pinfunction "OUT_14") (pintype "open_collector"))
      (node (ref "R87") (pin "1") (pinfunction "1_1") (pintype "passive"))
    )
    (net (code "98") (name "Net-(LED1-PadC)") (class "Default")
      (node (ref "LED1") (pin "C") (pinfunction "C_C") (pintype "passive"))
      (node (ref "R21") (pin "1") (pinfunction "1_1") (pintype "passive"))
    )
    (net (code "99") (name "Net-(Q1-G)") (class "Default")
      (node (ref "Q1") (pin "1") (pinfunction "G_1") (pintype "passive"))
      (node (ref "R6") (pin "1") (pinfunction "1_1") (pintype "passive"))
      (node (ref "R7") (pin "1") (pinfunction "1_1") (pintype "passive"))
    )
    (net (code "100") (name "Net-(Q1-S)") (class "Default")
      (node (ref "Q1") (pin "3") (pinfunction "S_3") (pintype "passive"))
      (node (ref "R2") (pin "2") (pinfunction "2_2") (pintype "passive"))
      (node (ref "R3") (pin "1") (pinfunction "1_1") (pintype "passive"))
      (node (ref "R6") (pin "2") (pinfunction "2_2") (pintype "passive"))
    )
    (net (code "101") (name "Net-(Q3-D)") (class "Default")
      (node (ref "Q2") (pin "C") (pinfunction "C_C") (pintype "passive"))
      (node (ref "Q3") (pin "3") (pinfunction "D_3") (pintype "passive"))
    )
    (net (code "102") (name "Net-(Q4-PadS)") (class "Default")
      (node (ref "Q4") (pin "S") (pinfunction "S_S") (pintype "passive"))
      (node (ref "R28") (pin "1") (pinfunction "1_1") (pintype "passive"))
      (node (ref "R28") (pin "1.1") (pinfunction "1_1.1") (pintype "passive"))
      (node (ref "R30") (pin "2") (pinfunction "2_2") (pintype "passive"))
      (node (ref "R31") (pin "2") (pinfunction "2_2") (pintype "passive"))
      (node (ref "R34") (pin "2") (pinfunction "2_2") (pintype "passive"))
      (node (ref "ZD2") (pin "A") (pinfunction "A_A") (pintype "passive"))
    )
    (net (code "103") (name "Net-(Q5-PadB)") (class "Default")
      (node (ref "Q5") (pin "B") (pinfunction "B_B") (pintype "passive"))
      (node (ref "R32") (pin "2") (pinfunction "2_2") (pintype "passive"))
    )
    (net (code "104") (name "Net-(Q6-PadB)") (class "Default")
      (node (ref "Q6") (pin "B") (pinfunction "B_B") (pintype "passive"))
      (node (ref "R31") (pin "1") (pinfunction "1_1") (pintype "passive"))
    )
    (net (code "105") (name "Net-(Q7-B)") (class "Default")
      (node (ref "D15") (pin "A") (pinfunction "A_A") (pintype "passive"))
      (node (ref "Q7") (pin "1") (pinfunction "B_1") (pintype "passive"))
      (node (ref "R38") (pin "2") (pinfunction "2_2") (pintype "passive"))
      (node (ref "R41") (pin "1") (pinfunction "1_1") (pintype "passive"))
    )
    (net (code "106") (name "Net-(Q7-E)") (class "Default")
      (node (ref "D12") (pin "A") (pinfunction "A_A") (pintype "passive"))
      (node (ref "Q7") (pin "3") (pinfunction "E_3") (pintype "passive"))
    )
    (net (code "107") (name "Net-(Q8-G)") (class "Default")
      (node (ref "D14") (pin "A") (pinfunction "A_A") (pintype "passive"))
      (node (ref "Q5") (pin "C") (pinfunction "C_C") (pintype "passive"))
      (node (ref "Q8") (pin "1") (pinfunction "G_1") (pintype "passive"))
      (node (ref "R33") (pin "2") (pinfunction "2_2") (pintype "passive"))
    )
    (net (code "108") (name "Net-(Q8-S)") (class "Default")
      (node (ref "Q8") (pin "3") (pinfunction "S_3") (pintype "passive"))
      (node (ref "R29") (pin "1") (pinfunction "1_1") (pintype "passive"))
      (node (ref "R29") (pin "1.1") (pinfunction "1_1.1") (pintype "passive"))
      (node (ref "R32") (pin "1") (pinfunction "1_1") (pintype "passive"))
      (node (ref "R33") (pin "1") (pinfunction "1_1") (pintype "passive"))
    )
    (net (code "109") (name "Net-(Q9-E)") (class "Default")
      (node (ref "Q9") (pin "3") (pinfunction "E_3") (pintype "passive"))
      (node (ref "R40") (pin "1") (pinfunction "1_1") (pintype "passive"))
    )
    (net (code "110") (name "Net-(Q10-PadB)") (class "Default")
      (node (ref "Q10") (pin "B") (pinfunction "B_B") (pintype "passive"))
      (node (ref "Q10") (pin "C") (pinfunction "C_C") (pintype "passive"))
      (node (ref "Q11") (pin "B") (pinfunction "B_B") (pintype "passive"))
      (node (ref "Q13") (pin "C") (pinfunction "C_C") (pintype "passive"))
    )
    (net (code "111") (name "Net-(Q10-PadE)") (class "Default")
      (node (ref "Q10") (pin "E") (pinfunction "E_E") (pintype "passive"))
      (node (ref "R36") (pin "1") (pinfunction "1_1") (pintype "passive"))
    )
    (net (code "112") (name "Net-(Q11-PadC)") (class "Default")
      (node (ref "Q11") (pin "C") (pinfunction "C_C") (pintype "passive"))
      (node (ref "Q12") (pin "C") (pinfunction "C_C") (pintype "passive"))
      (node (ref "R41") (pin "2") (pinfunction "2_2") (pintype "passive"))
      (node (ref "R48") (pin "2") (pinfunction "2_2") (pintype "passive"))
    )
    (net (code "113") (name "Net-(Q11-PadE)") (class "Default")
      (node (ref "Q11") (pin "E") (pinfunction "E_E") (pintype "passive"))
      (node (ref "R37") (pin "1") (pinfunction "1_1") (pintype "passive"))
    )
    (net (code "114") (name "Net-(Q12-PadB)") (class "Default")
      (node (ref "Q12") (pin "B") (pinfunction "B_B") (pintype "passive"))
      (node (ref "R34") (pin "1") (pinfunction "1_1") (pintype "passive"))
      (node (ref "R44") (pin "2") (pinfunction "2_2") (pintype "passive"))
    )
    (net (code "115") (name "Net-(Q12-PadE)") (class "Default")
      (node (ref "Q12") (pin "E") (pinfunction "E_E") (pintype "passive"))
      (node (ref "R50") (pin "2") (pinfunction "2_2") (pintype "passive"))
    )
    (net (code "116") (name "Net-(Q13-PadE)") (class "Default")
      (node (ref "Q13") (pin "E") (pinfunction "E_E") (pintype "passive"))
      (node (ref "R53") (pin "2") (pinfunction "2_2") (pintype "passive"))
    )
    (net (code "117") (name "Net-(Q14-D)") (class "Default")
      (node (ref "Q14") (pin "3") (pinfunction "D_3") (pintype "passive"))
      (node (ref "R74") (pin "2") (pinfunction "2_2") (pintype "passive"))
    )
    (net (code "118") (name "Net-(R15-Pad2)") (class "Default")
      (node (ref "R15") (pin "2") (pinfunction "2_2") (pintype "passive"))
      (node (ref "ZD1") (pin "C") (pinfunction "C_C") (pintype "passive"))
    )
    (net (code "119") (name "Net-(R60-Pad2)") (class "Default")
      (node (ref "R60") (pin "2") (pinfunction "2_2") (pintype "passive"))
      (node (ref "R61") (pin "1") (pinfunction "1_1") (pintype "passive"))
    )
    (net (code "120") (name "Net-(R63-Pad1)") (class "Default")
      (node (ref "R63") (pin "1") (pinfunction "1_1") (pintype "passive"))
      (node (ref "R64") (pin "2") (pinfunction "2_2") (pintype "passive"))
    )
    (net (code "121") (name "Net-(R67-Pad1)") (class "Default")
      (node (ref "R67") (pin "1") (pinfunction "1_1") (pintype "passive"))
      (node (ref "R68") (pin "2") (pinfunction "2_2") (pintype "passive"))
    )
    (net (code "122") (name "Net-(R69-Pad1)") (class "Default")
      (node (ref "R69") (pin "1") (pinfunction "1_1") (pintype "passive"))
      (node (ref "R70") (pin "2") (pinfunction "2_2") (pintype "passive"))
    )
    (net (code "123") (name "OUT+") (class "Default")
      (node (ref "C47") (pin "2") (pinfunction "2_2") (pintype "passive"))
      (node (ref "C50") (pin "1") (pinfunction "1_1") (pintype "passive"))
      (node (ref "C63") (pin "1") (pinfunction "1_1") (pintype "passive"))
      (node (ref "Q5") (pin "E") (pinfunction "E_E") (pintype "passive"))
      (node (ref "Q6") (pin "E") (pinfunction "E_E") (pintype "passive"))
      (node (ref "R28") (pin "2") (pinfunction "2_2") (pintype "passive"))
      (node (ref "R28") (pin "2.1") (pinfunction "2_2.1") (pintype "passive"))
      (node (ref "R29") (pin "2") (pinfunction "2_2") (pintype "passive"))
      (node (ref "R29") (pin "2.1") (pinfunction "2_2.1") (pintype "passive"))
      (node (ref "R35") (pin "1") (pinfunction "1_1") (pintype "passive"))
      (node (ref "X4") (pin "23") (pinfunction "1_23") (pintype "passive"))
      (node (ref "X4") (pin "24") (pinfunction "1_24") (pintype "passive"))
      (node (ref "X4") (pin "25") (pinfunction "1_25") (pintype "passive"))
      (node (ref "X4") (pin "26") (pinfunction "1_26") (pintype "passive"))
      (node (ref "ZD1") (pin "A") (pinfunction "A_A") (pintype "passive"))
    )
    (net (code "124") (name "OUT-") (class "Default")
      (node (ref "C46") (pin "1") (pinfunction "1_1") (pintype "passive"))
      (node (ref "C48") (pin "2") (pinfunction "2_2") (pintype "passive"))
      (node (ref "R59") (pin "2") (pinfunction "2_2") (pintype "passive"))
      (node (ref "R64") (pin "1") (pinfunction "1_1") (pintype "passive"))
      (node (ref "R66") (pin "1") (pinfunction "1_1") (pintype "passive"))
      (node (ref "X4") (pin "17") (pinfunction "1_17") (pintype "passive"))
      (node (ref "X4") (pin "18") (pinfunction "1_18") (pintype "passive"))
      (node (ref "X4") (pin "19") (pinfunction "1_19") (pintype "passive"))
      (node (ref "X4") (pin "20") (pinfunction "1_20") (pintype "passive"))
    )
    (net (code "125") (name "POST_OE") (class "Default")
      (node (ref "Q15") (pin "3") (pinfunction "D_3") (pintype "passive"))
      (node (ref "R53") (pin "1") (pinfunction "1_1") (pintype "passive"))
    )
    (net (code "126") (name "POUT-") (class "Default")
      (node (ref "C11") (pin "2") (pinfunction "2_2") (pintype "passive"))
      (node (ref "C12") (pin "2") (pinfunction "2_2") (pintype "passive"))
      (node (ref "C13") (pin "2") (pinfunction "2_2") (pintype "passive"))
      (node (ref "C14") (pin "2") (pinfunction "2_2") (pintype "passive"))
      (node (ref "C17") (pin "1") (pinfunction "1_1") (pintype "passive"))
      (node (ref "R66") (pin "2") (pinfunction "2_2") (pintype "passive"))
      (node (ref "R68") (pin "1") (pinfunction "1_1") (pintype "passive"))
      (node (ref "SH1") (pin "1") (pinfunction "GND_A_1") (pintype "bidirectional"))
    )
    (net (code "127") (name "PREG_OUT") (class "Default")
      (node (ref "FB1") (pin "2") (pinfunction "2_2") (pintype "passive"))
      (node (ref "Q4") (pin "D") (pinfunction "D_D") (pintype "passive"))
    )
    (net (code "128") (name "PRE_OE") (class "Default")
      (node (ref "IC10") (pin "17") (pinfunction "GP7_17") (pintype "bidirectional"))
      (node (ref "OE") (pin "1") (pinfunction "P$1_1") (pintype "bidirectional"))
      (node (ref "Q15") (pin "1") (pinfunction "G_1") (pintype "passive"))
      (node (ref "R4") (pin "2") (pinfunction "2_2") (pintype "passive"))
      (node (ref "R75") (pin "2") (pinfunction "2_2") (pintype "passive"))
    )
    (net (code "129") (name "PS_MISO") (class "Default")
      (node (ref "IC10") (pin "3") (pinfunction "SO_3") (pintype "output"))
      (node (ref "IC13") (pin "15") (pinfunction "DOUT/~{DRDY}_15") (pintype "output"))
      (node (ref "X4") (pin "9") (pinfunction "1_9") (pintype "passive"))
    )
    (net (code "130") (name "PS_MOSI") (class "Default")
      (node (ref "IC10") (pin "2") (pinfunction "SI_2") (pintype "input"))
      (node (ref "IC11") (pin "7") (pinfunction "DIN_7") (pintype "input"))
      (node (ref "IC13") (pin "16") (pinfunction "DIN_16") (pintype "input"))
      (node (ref "X4") (pin "1") (pinfunction "1_1") (pintype "passive"))
    )
    (net (code "131") (name "PS_SCLK") (class "Default")
      (node (ref "IC10") (pin "1") (pinfunction "SCK_1") (pintype "input"))
      (node (ref "IC11") (pin "6") (pinfunction "SCLK_6") (pintype "input"))
      (node (ref "IC13") (pin "1") (pinfunction "SCLK_1") (pintype "input"))
      (node (ref "X4") (pin "7") (pinfunction "1_7") (pintype "passive"))
    )
    (net (code "132") (name "PWRGOOD") (class "Default")
      (node (ref "IC10") (pin "16") (pinfunction "GP6_16") (pintype "bidirectional"))
      (node (ref "IC6") (pin "5") (pinfunction "~{ERROR}_5") (pintype "input"))
      (node (ref "R27") (pin "2") (pinfunction "2_2") (pintype "passive"))
    )
    (net (code "133") (name "SENSE+") (class "Default")
      (node (ref "C45") (pin "1") (pinfunction "1_1") (pintype "passive"))
      (node (ref "R35") (pin "2") (pinfunction "2_2") (pintype "passive"))
      (node (ref "R47") (pin "2") (pinfunction "2_2") (pintype "passive"))
      (node (ref "X4") (pin "22") (pinfunction "1_22") (pintype "passive"))
    )
    (net (code "134") (name "SENSE-") (class "Default")
      (node (ref "C51") (pin "1") (pinfunction "1_1") (pintype "passive"))
      (node (ref "R57") (pin "2") (pinfunction "2_2") (pintype "passive"))
      (node (ref "R59") (pin "1") (pinfunction "1_1") (pintype "passive"))
      (node (ref "X4") (pin "21") (pinfunction "1_21") (pintype "passive"))
    )
    (net (code "135") (name "SGND") (class "Default")
      (node (ref "C19") (pin "2") (pinfunction "2_2") (pintype "passive"))
      (node (ref "C21") (pin "2") (pinfunction "2_2") (pintype "passive"))
      (node (ref "C9") (pin "1") (pinfunction "1_1") (pintype "passive"))
      (node (ref "IC1") (pin "3") (pinfunction "SGND_3") (pintype "passive"))
      (node (ref "JMP1") (pin "1") (pinfunction "1_1") (pintype "passive"))
      (node (ref "R16") (pin "2") (pinfunction "2_2") (pintype "passive"))
      (node (ref "R5") (pin "2") (pinfunction "2_2") (pintype "passive"))
      (node (ref "SH2") (pin "1") (pinfunction "GND_A_1") (pintype "bidirectional"))
    )
    (net (code "136") (name "SYNC") (class "Default")
      (node (ref "IC2") (pin "2") (pinfunction "A1_2") (pintype "input"))
      (node (ref "IC5") (pin "4") (pinfunction "SYNC_4") (pintype "input"))
      (node (ref "JMP1") (pin "3") (pinfunction "3_3") (pintype "passive"))
      (node (ref "X2") (pin "4") (pinfunction "1_4") (pintype "passive"))
    )
    (net (code "137") (name "TEMP_NTC") (class "Default")
      (node (ref "X3") (pin "1") (pinfunction "1_1") (pintype "passive"))
      (node (ref "X4") (pin "13") (pinfunction "1_13") (pintype "passive"))
    )
    (net (code "138") (name "U_MON") (class "Default")
      (node (ref "IC13") (pin "10") (pinfunction "AIN1_10") (pintype "input"))
      (node (ref "IC7") (pin "7") (pinfunction "OUT_7") (pintype "output"))
      (node (ref "R51") (pin "1") (pinfunction "1_1") (pintype "passive"))
      (node (ref "R52") (pin "1") (pinfunction "1_1") (pintype "passive"))
    )
    (net (code "139") (name "U_SERVO") (class "Default")
      (node (ref "CV") (pin "1") (pinfunction "P$1_1") (pintype "bidirectional"))
      (node (ref "D16") (pin "C") (pinfunction "C_C") (pintype "passive"))
      (node (ref "D17") (pin "A") (pinfunction "A_A") (pintype "passive"))
      (node (ref "IC7") (pin "1") (pinfunction "OUT_1") (pintype "output"))
      (node (ref "R54") (pin "2") (pinfunction "2_2") (pintype "passive"))
      (node (ref "R79") (pin "1") (pinfunction "1_1") (pintype "passive"))
    )
    (net (code "140") (name "U_SET") (class "Default")
      (node (ref "IC15") (pin "5") (pinfunction "D_5") (pintype "bidirectional"))
      (node (ref "R49") (pin "1") (pinfunction "1_1") (pintype "passive"))
      (node (ref "R77") (pin "1") (pinfunction "1_1") (pintype "passive"))
    )
    (net (code "141") (name "U_SET_IN") (class "Default")
      (node (ref "IC11") (pin "4") (pinfunction "VOUTA_4") (pintype "output"))
      (node (ref "IC13") (pin "11") (pinfunction "AIN0/REFP1_11") (pintype "input"))
      (node (ref "X5") (pin "1") (pinfunction "1_1") (pintype "passive"))
    )
    (net (code "142") (name "U_SET_OUT") (class "Default")
      (node (ref "IC15") (pin "4") (pinfunction "S2_4") (pintype "bidirectional"))
      (node (ref "R77") (pin "2") (pinfunction "2_2") (pintype "passive"))
      (node (ref "X5") (pin "3") (pinfunction "1_3") (pintype "passive"))
    )
    (net (code "143") (name "V+") (class "Default")
      (node (ref "C52") (pin "2") (pinfunction "2_2") (pintype "passive"))
      (node (ref "C53") (pin "1") (pinfunction "1_1") (pintype "passive"))
      (node (ref "C54") (pin "2") (pinfunction "2_2") (pintype "passive"))
      (node (ref "C55") (pin "2") (pinfunction "2_2") (pintype "passive"))
      (node (ref "C56") (pin "2") (pinfunction "2_2") (pintype "passive"))
      (node (ref "C75") (pin "2") (pinfunction "2_2") (pintype "passive"))
      (node (ref "FB2") (pin "P$2") (pinfunction "2_P$2") (pintype "passive"))
      (node (ref "IC14") (pin "6") (pinfunction "VDD_6") (pintype "bidirectional"))
      (node (ref "IC15") (pin "2") (pinfunction "VDD_2") (pintype "power_in"))
      (node (ref "IC16") (pin "3") (pinfunction "V+_3") (pintype "power_in"))
      (node (ref "IC7") (pin "8") (pinfunction "V+_8") (pintype "power_in"))
      (node (ref "IC8") (pin "8") (pinfunction "V+_8") (pintype "power_in"))
      (node (ref "IC9") (pin "7") (pinfunction "V+_7") (pintype "power_in"))
      (node (ref "R81") (pin "2") (pinfunction "2_2") (pintype "passive"))
    )
    (net (code "144") (name "V-") (class "Default")
      (node (ref "C57") (pin "2") (pinfunction "2_2") (pintype "passive"))
      (node (ref "C58") (pin "2") (pinfunction "2_2") (pintype "passive"))
      (node (ref "C59") (pin "1") (pinfunction "1_1") (pintype "passive"))
      (node (ref "C60") (pin "2") (pinfunction "2_2") (pintype "passive"))
      (node (ref "C61") (pin "2") (pinfunction "2_2") (pintype "passive"))
      (node (ref "C76") (pin "2") (pinfunction "2_2") (pintype "passive"))
      (node (ref "FB") (pin "P$2") (pinfunction "2_P$2") (pintype "passive"))
      (node (ref "IC14") (pin "3") (pinfunction "VSS_3") (pintype "bidirectional"))
      (node (ref "IC16") (pin "12") (pinfunction "GND_12") (pintype "power_in"))
      (node (ref "IC7") (pin "4") (pinfunction "V-_4") (pintype "power_in"))
      (node (ref "IC8") (pin "4") (pinfunction "V-_4") (pintype "power_in"))
      (node (ref "IC9") (pin "4") (pinfunction "V-_4") (pintype "power_in"))
      (node (ref "R86") (pin "1") (pinfunction "1_1") (pintype "passive"))
    )
    (net (code "145") (name "VBIAS") (class "Default")
      (node (ref "BIAS") (pin "1") (pinfunction "P$1_1") (pintype "bidirectional"))
      (node (ref "C43") (pin "1") (pinfunction "1_1") (pintype "passive"))
      (node (ref "C5") (pin "+") (pinfunction "+_+") (pintype "passive"))
      (node (ref "C5") (pin "+.1") (pinfunction "+_+.1") (pintype "passive"))
      (node (ref "D5") (pin "C") (pinfunction "C_C") (pintype "passive"))
      (node (ref "Q7") (pin "2") (pinfunction "C_2") (pintype "passive"))
      (node (ref "Q7") (pin "4") (pinfunction "C_4") (pintype "passive"))
      (node (ref "R36") (pin "2") (pinfunction "2_2") (pintype "passive"))
      (node (ref "R37") (pin "2") (pinfunction "2_2") (pintype "passive"))
    )
    (net (code "146") (name "unconnected-(IC1-PGOOD-Pad7)") (class "Default")
      (node (ref "IC1") (pin "7") (pinfunction "PGOOD_7") (pintype "output"))
    )
    (net (code "147") (name "unconnected-(IC6-SD-Pad3)") (class "Default")
      (node (ref "IC6") (pin "3") (pinfunction "SD_3") (pintype "input"))
    )
    (net (code "148") (name "unconnected-(IC6-SENSE-Pad2)") (class "Default")
      (node (ref "IC6") (pin "2") (pinfunction "SENSE_2") (pintype "input"))
    )
    (net (code "149") (name "unconnected-(IC6-VTAP-Pad6)") (class "Default")
      (node (ref "IC6") (pin "6") (pinfunction "VTAP_6") (pintype "input"))
    )
    (net (code "150") (name "unconnected-(IC12-TEMP-Pad3)") (class "Default")
      (node (ref "IC12") (pin "3") (pinfunction "TEMP_3") (pintype "input"))
    )
    (net (code "151") (name "~{DP_DRIVE}") (class "Default")
      (node (ref "Q9") (pin "1") (pinfunction "B_1") (pintype "passive"))
      (node (ref "R39") (pin "1") (pinfunction "1_1") (pintype "passive"))
      (node (ref "R74") (pin "1") (pinfunction "1_1") (pintype "passive"))
    )
    (net (code "152") (name "~{INT}") (class "Default")
      (node (ref "JMP2") (pin "3") (pinfunction "3_3") (pintype "passive"))
      (node (ref "X4") (pin "8") (pinfunction "1_8") (pintype "passive"))
    )
    (net (code "153") (name "~{PS_DRDY}") (class "Default")
      (node (ref "IC13") (pin "14") (pinfunction "~{DRDY}_14") (pintype "output"))
      (node (ref "JMP2") (pin "2") (pinfunction "2_2") (pintype "passive"))
    )
    (net (code "154") (name "~{PS_RESET}") (class "Default")
      (node (ref "IC10") (pin "6") (pinfunction "~{RESET}_6") (pintype "input"))
      (node (ref "X4") (pin "5") (pinfunction "1_5") (pintype "passive"))
    )
    (net (code "155") (name "~{SET_100%}") (class "Default")
      (node (ref "IC10") (pin "13") (pinfunction "GP3_13") (pintype "bidirectional"))
      (node (ref "Q3") (pin "1") (pinfunction "G_1") (pintype "passive"))
    )
    (net (code "156") (name "~{SET_DP}") (class "Default")
      (node (ref "IC10") (pin "11") (pinfunction "GP1_11") (pintype "bidirectional"))
      (node (ref "Q14") (pin "1") (pinfunction "G_1") (pintype "passive"))
      (node (ref "R73") (pin "2") (pinfunction "2_2") (pintype "passive"))
    )
  )
)
